# TK90X.net
KiCad netlist of a schematic drawn in EAGLE
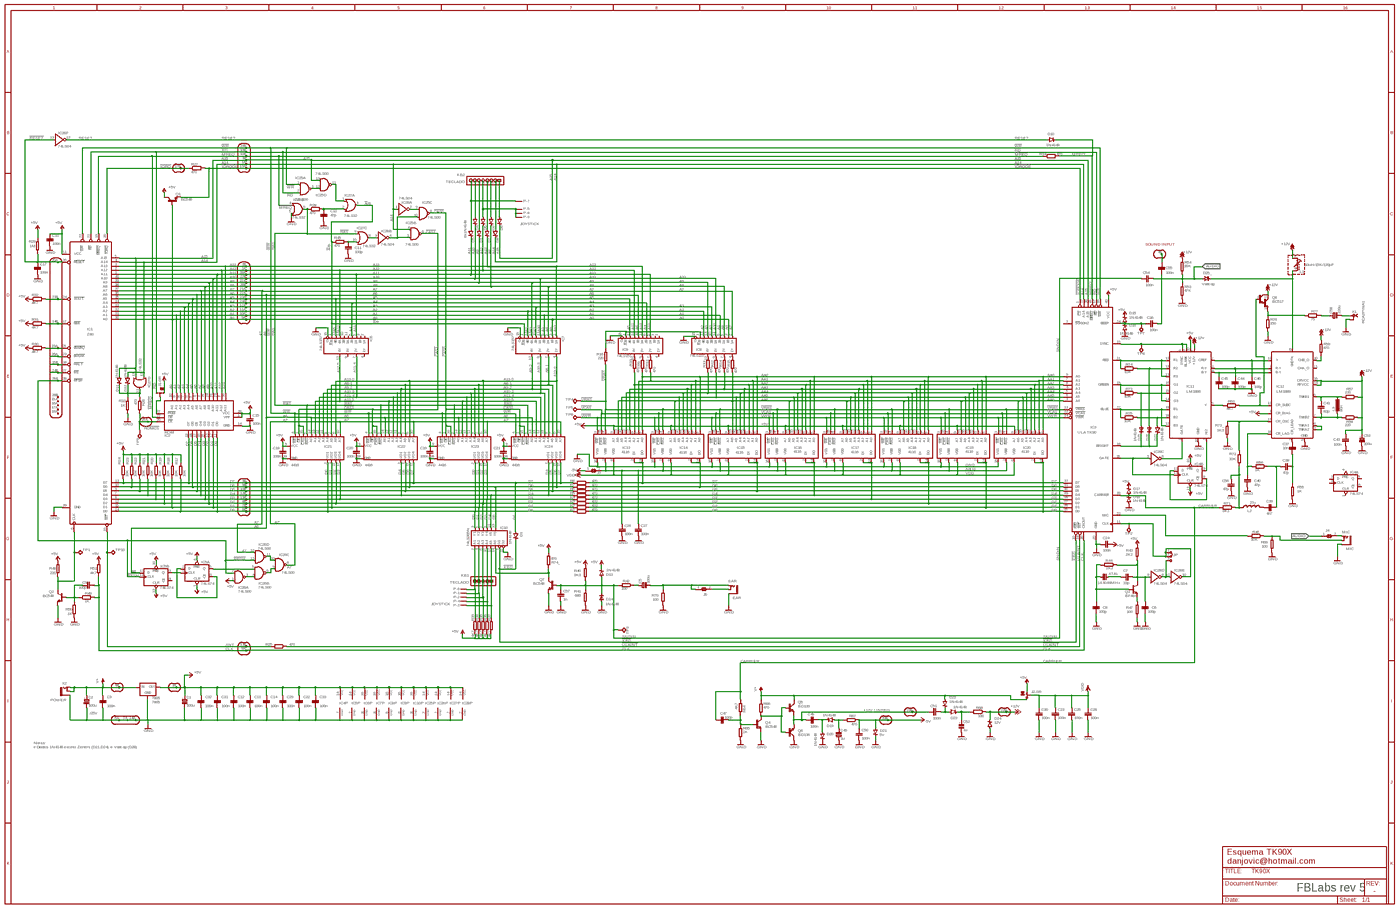
[diagram p0: schematic, sheet 1, overview]
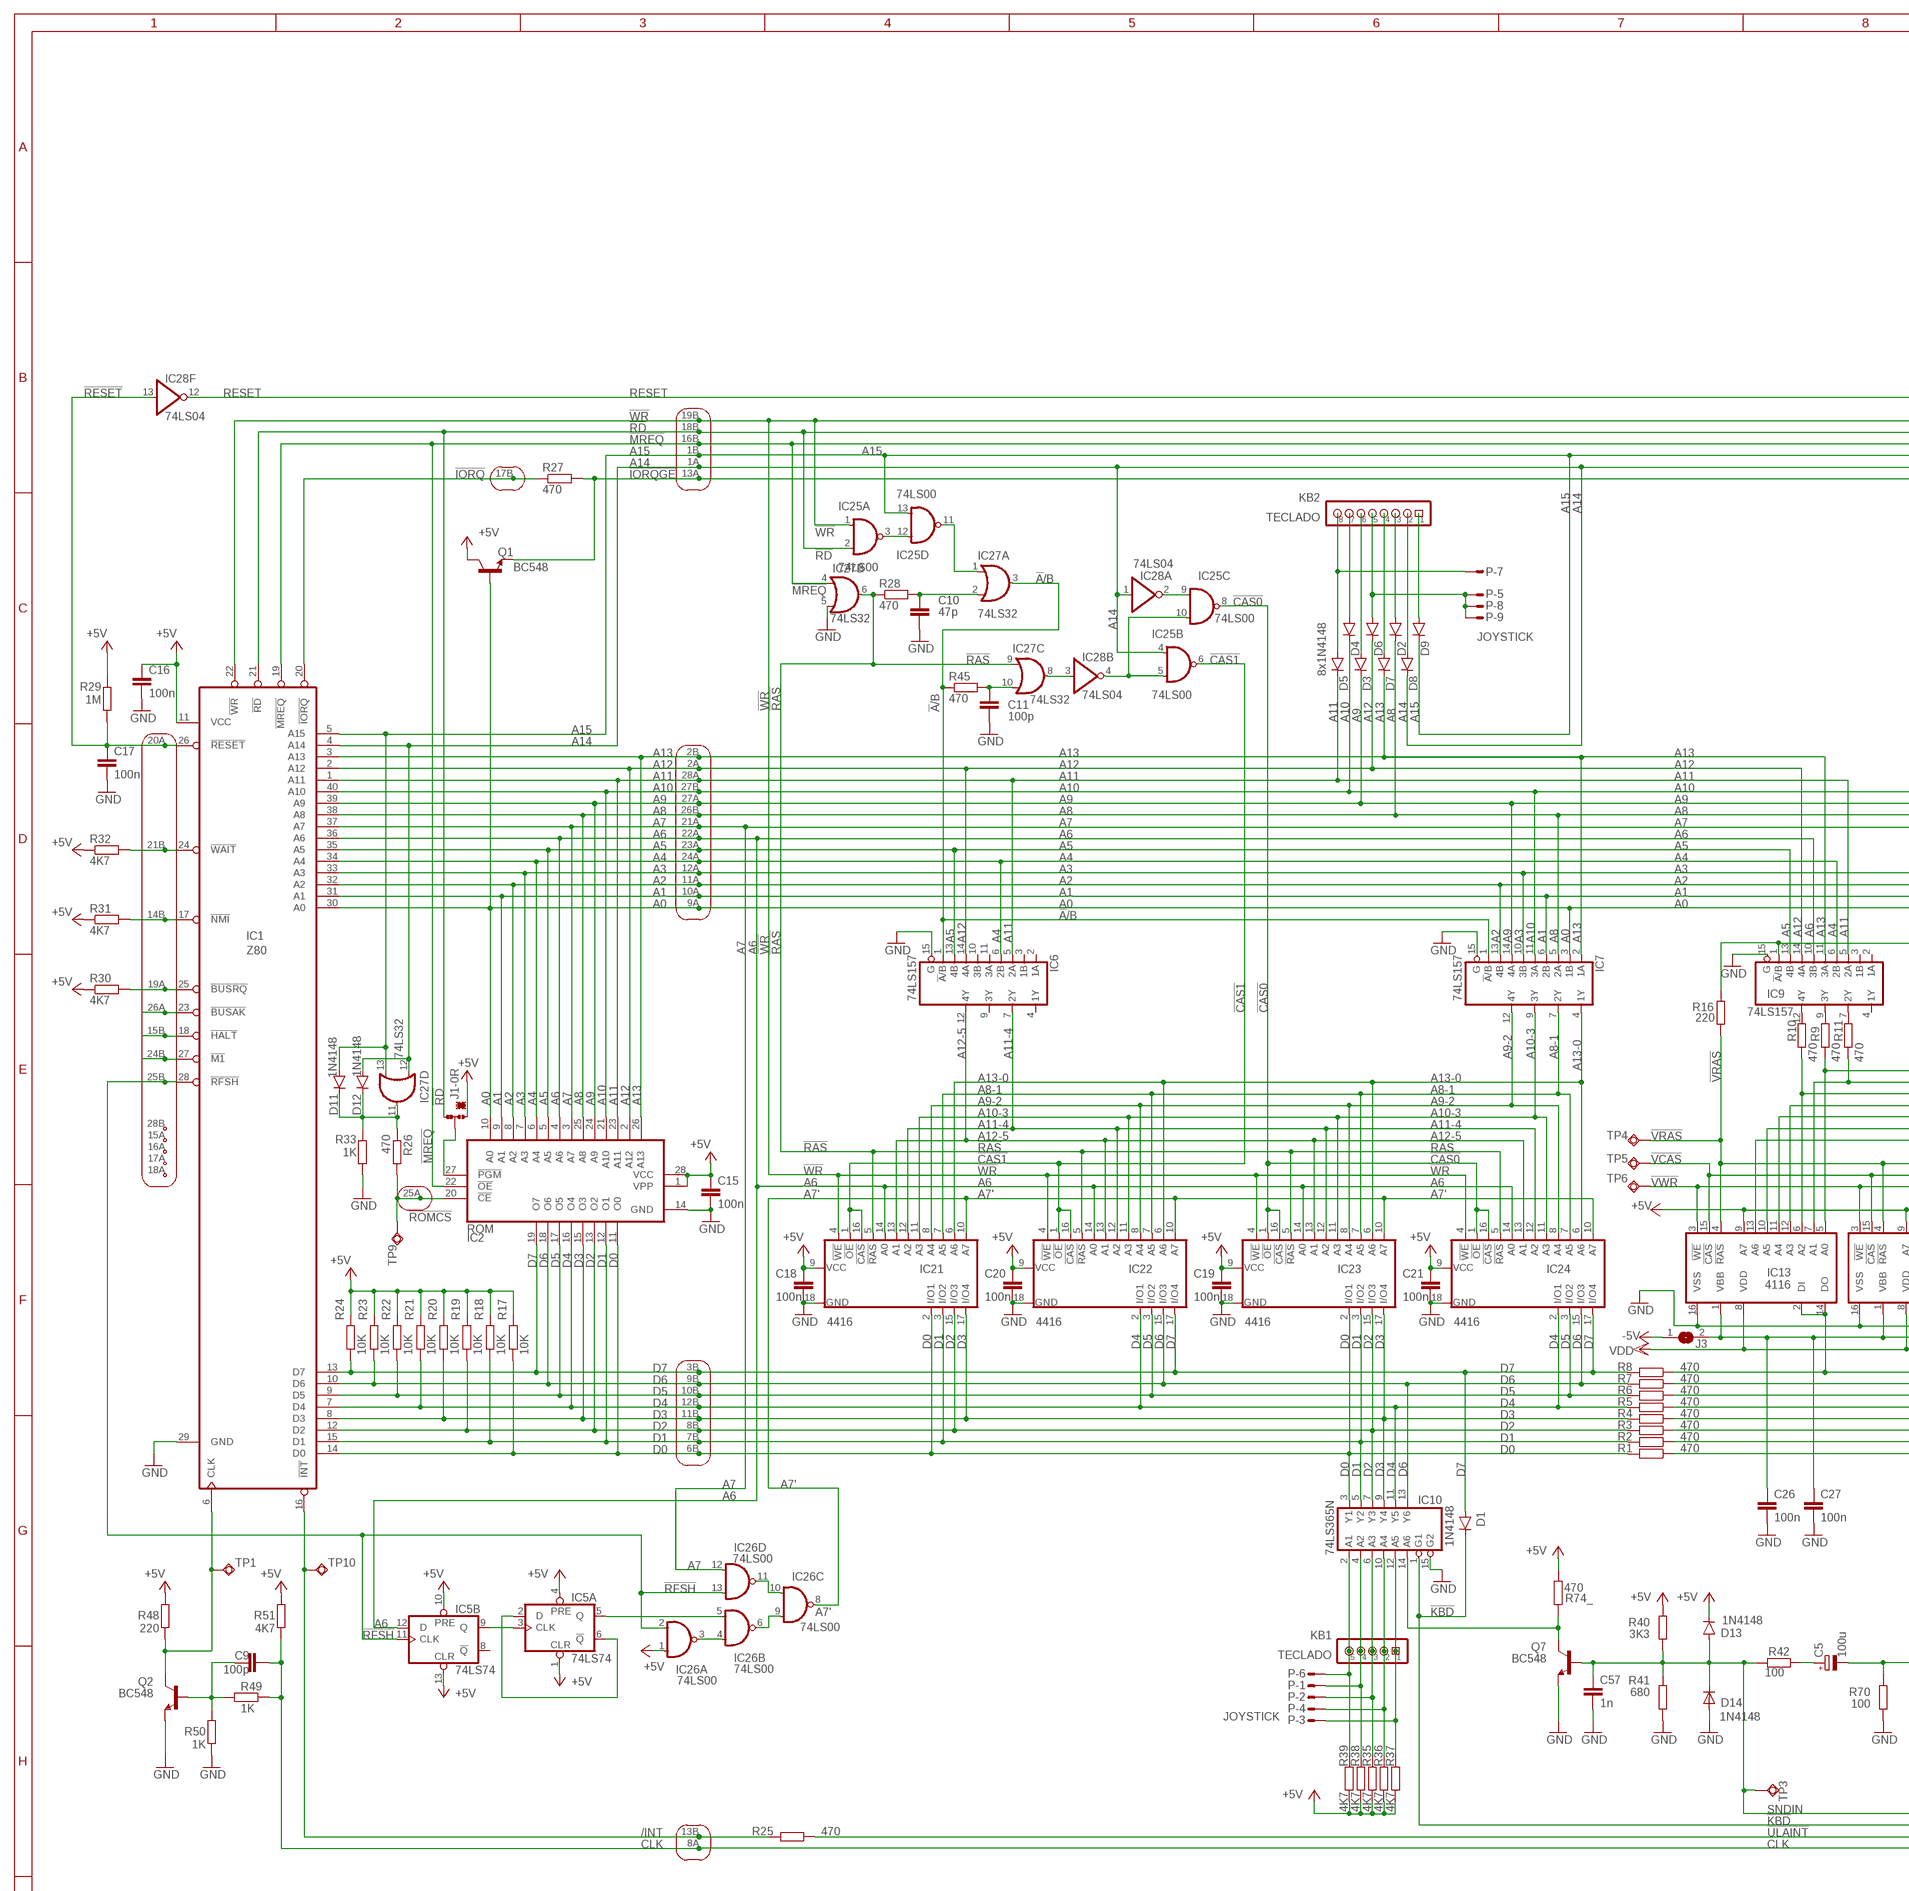
[diagram p1: schematic, sheet 1, part 1 of 4]
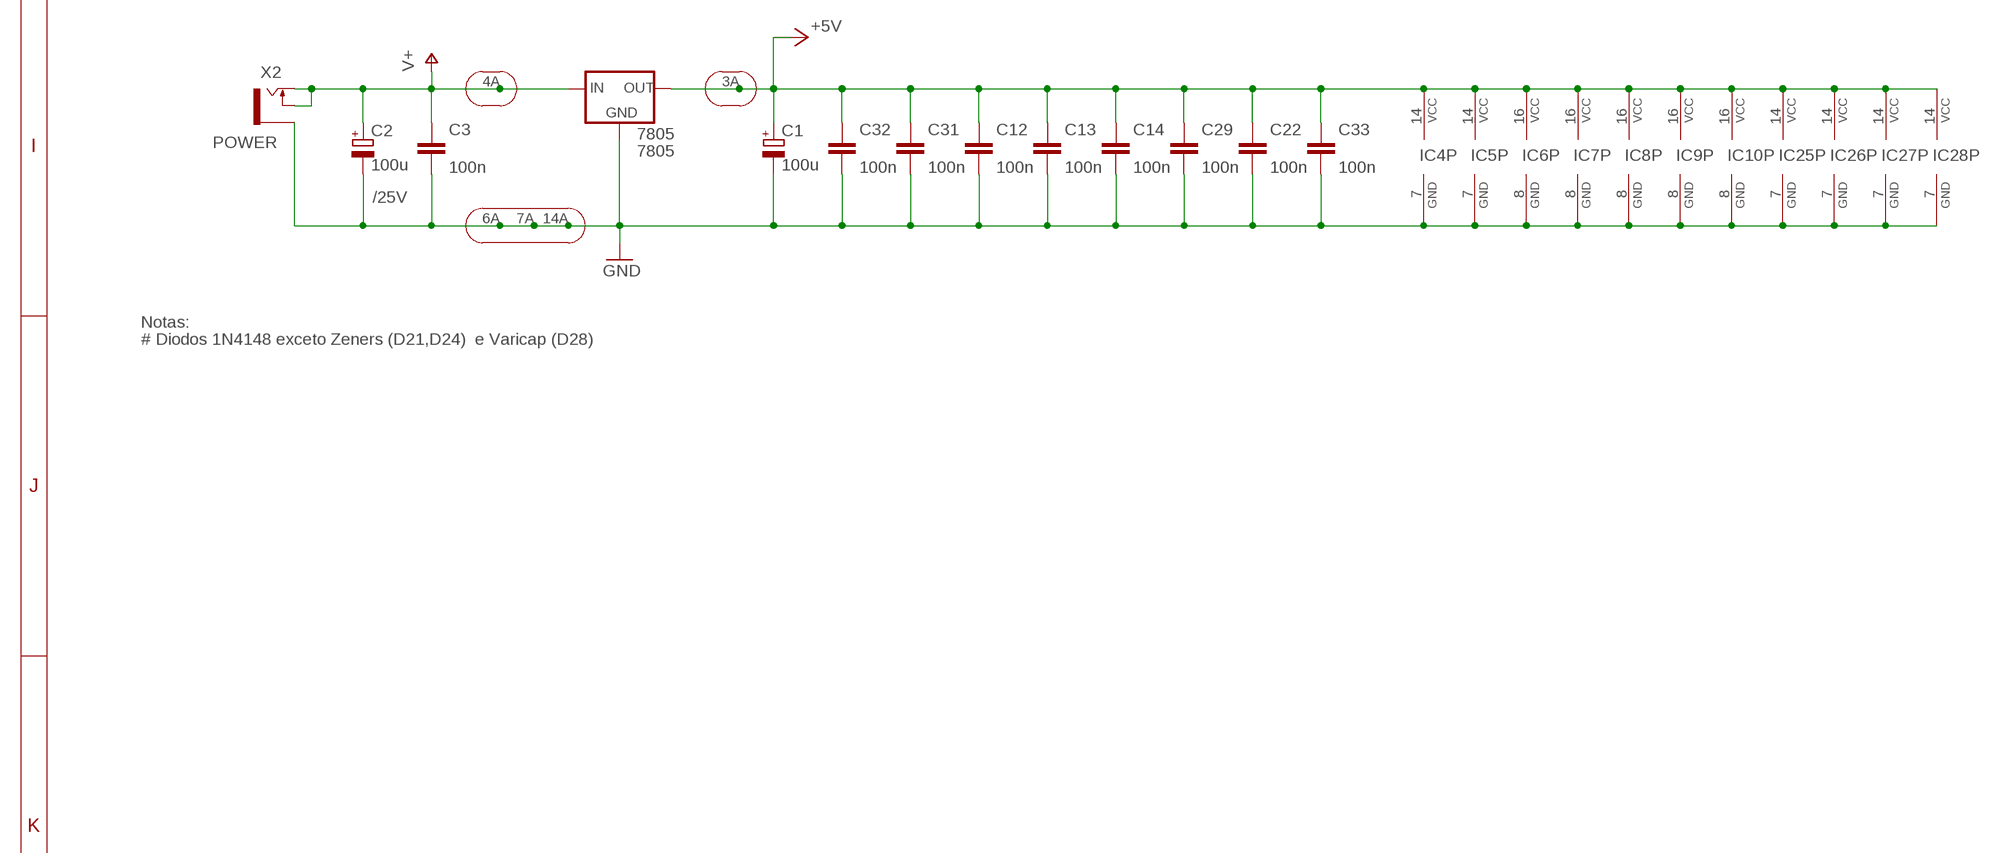
[diagram p2: schematic, sheet 1, part 2 of 4]
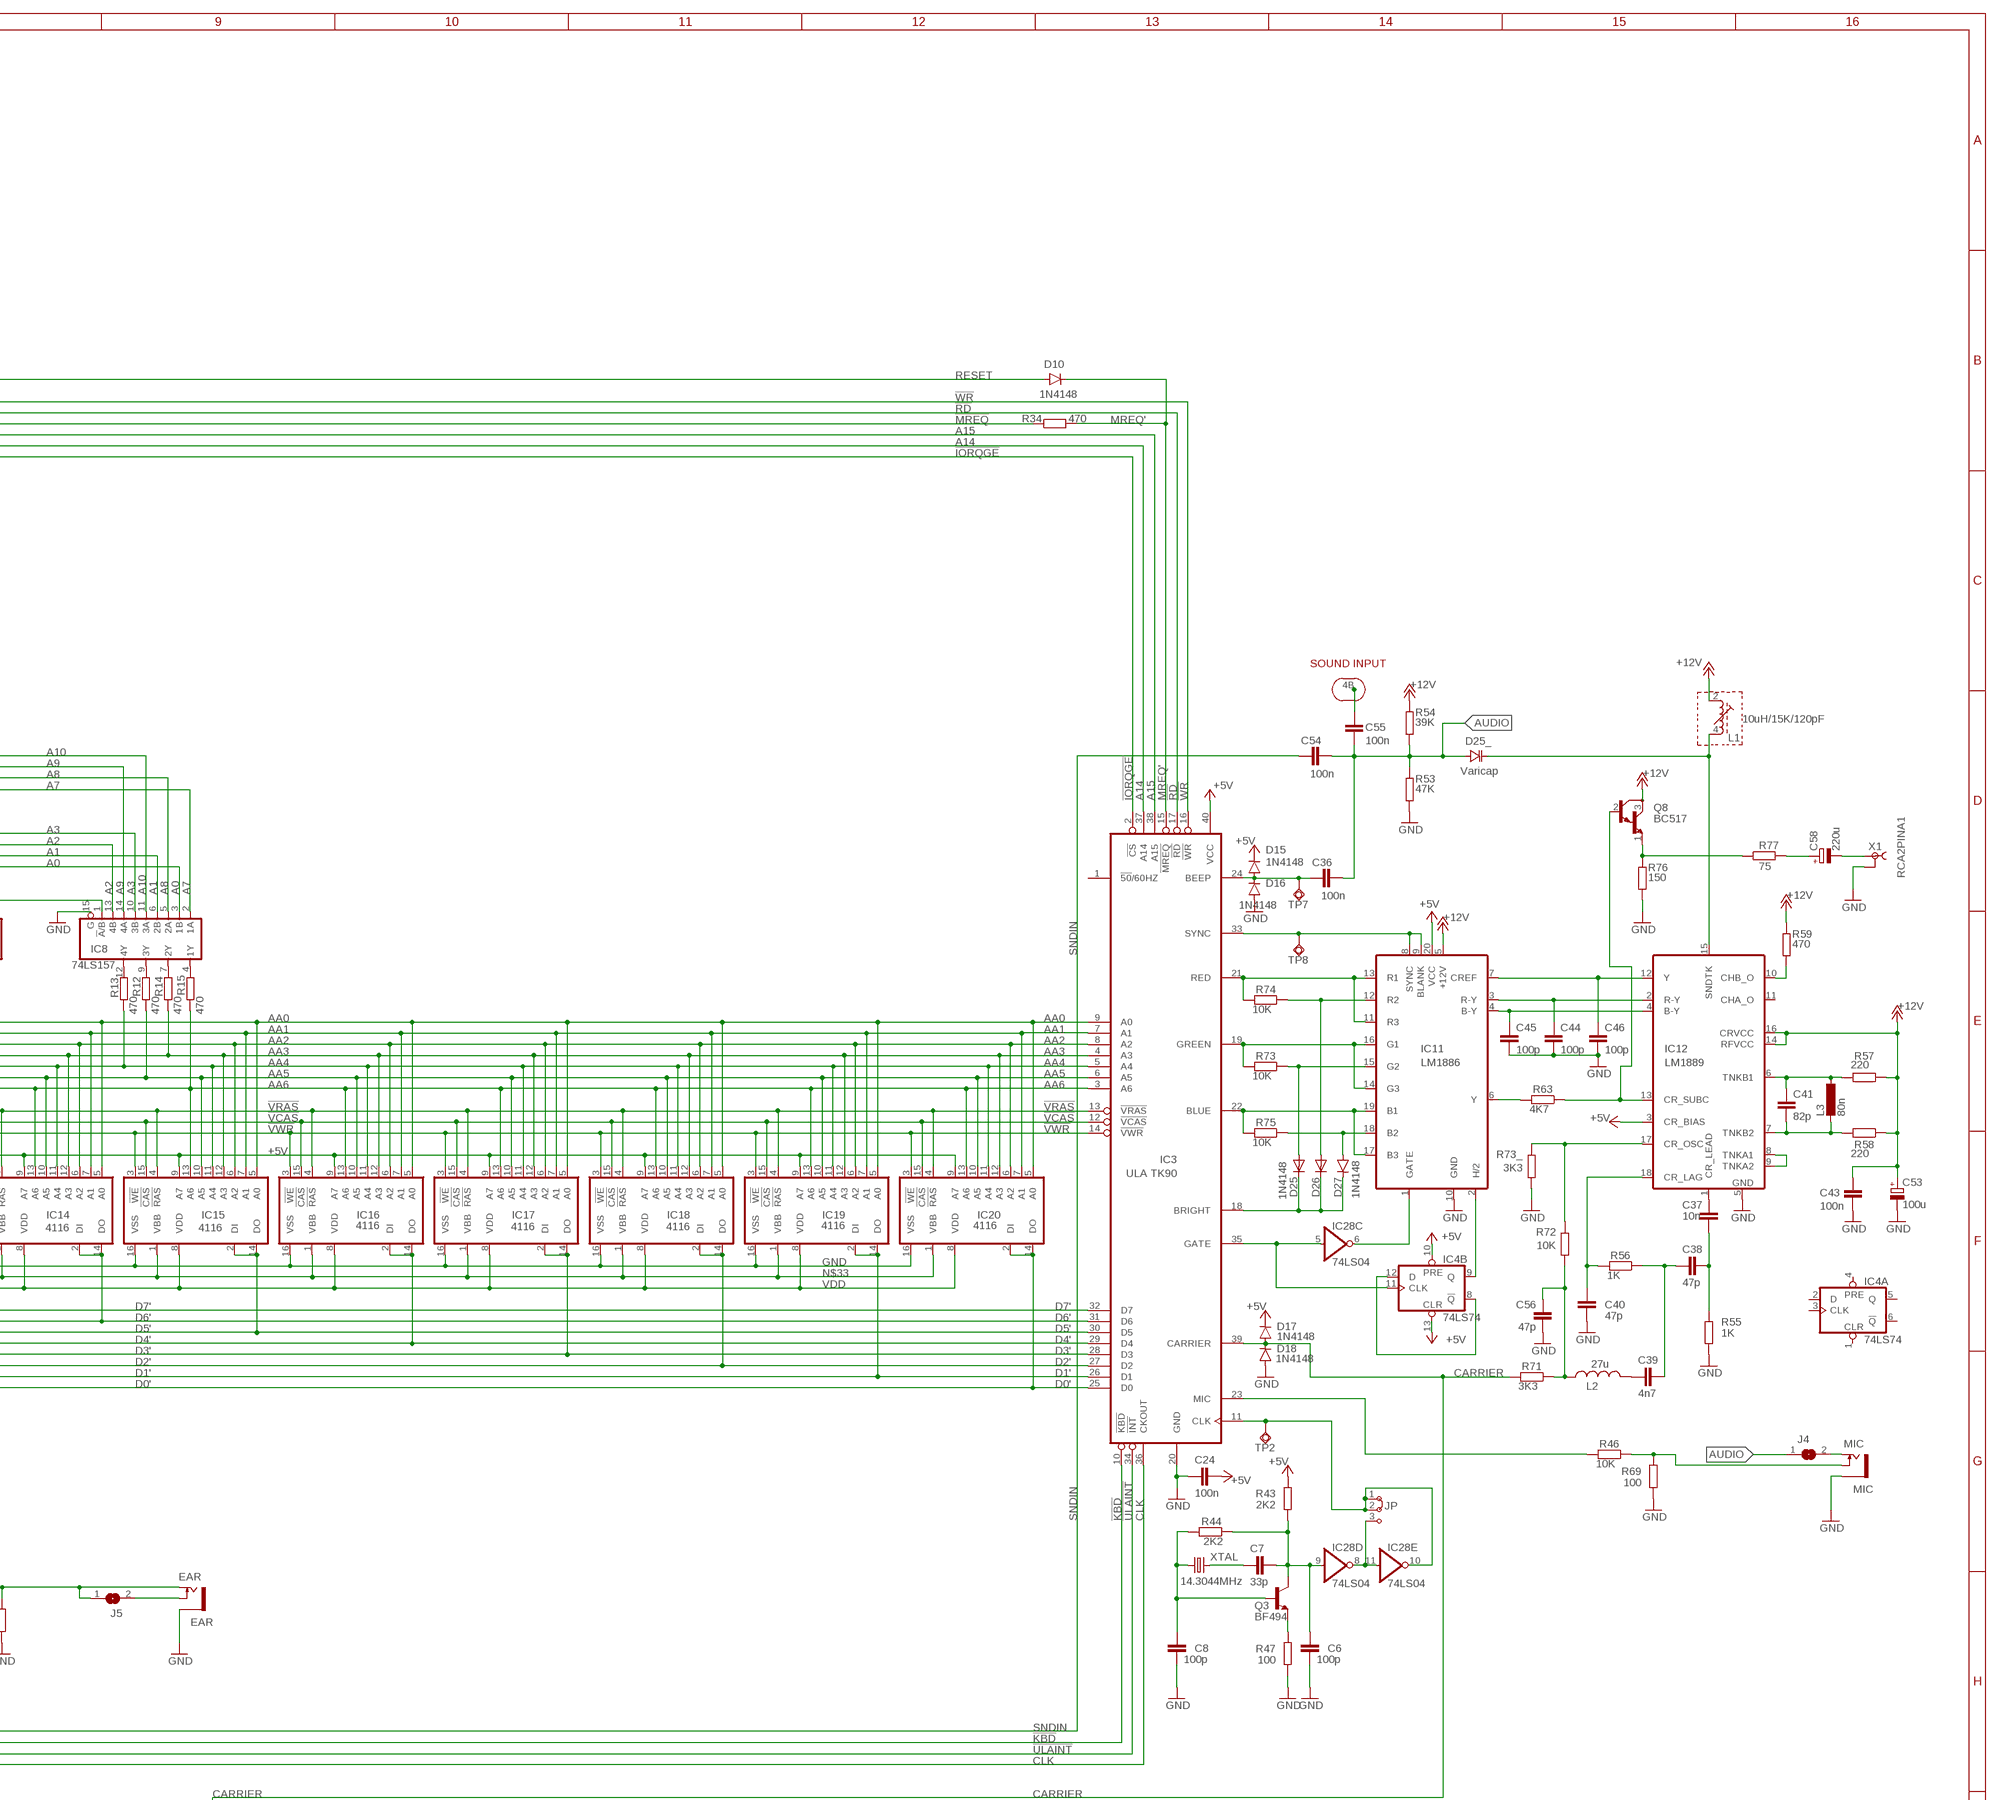
[diagram p3: schematic, sheet 1, part 3 of 4]
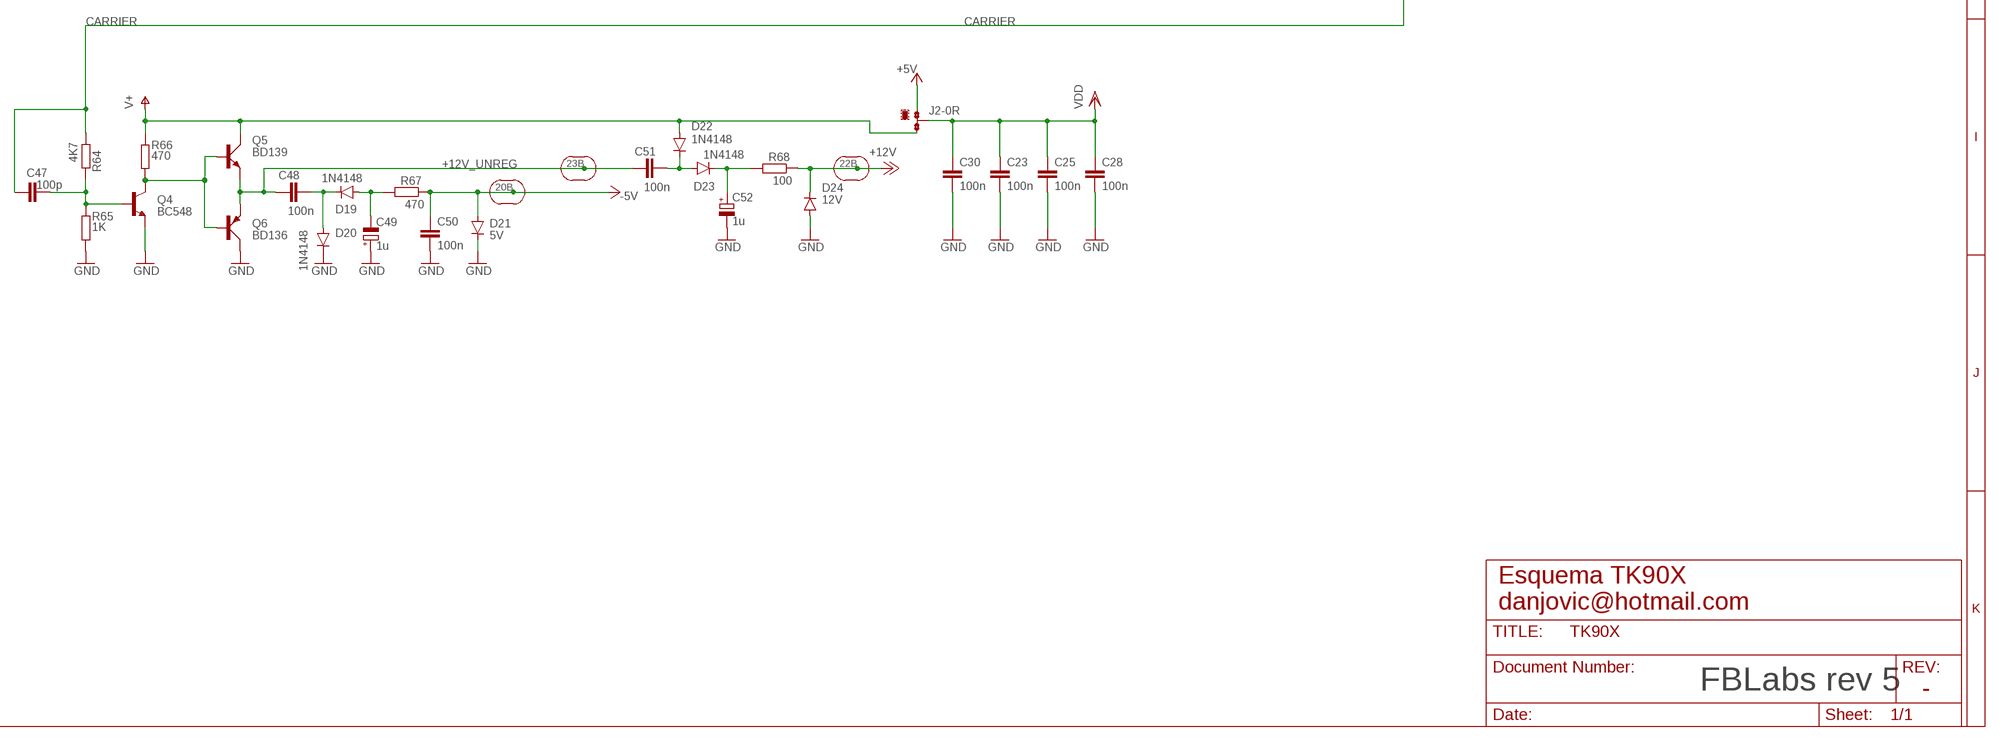
[diagram p4: schematic, sheet 1, part 4 of 4]

(export (version "E")
  (design (tool "Eeschema 10.0.6"))
  (components
    (comp (ref "7805")
      (value "7805")
      (footprint "eagle-import:78XXL")
      (libsource (lib "eagle-import") (part "78XXL"))
    )
    (comp (ref "C1")
      (value "100u")
      (footprint "eagle-import:E5-8,5")
      (libsource (lib "eagle-import") (part "CPOL-EUE5-8.5"))
    )
    (comp (ref "C2")
      (value "100u")
      (footprint "eagle-import:E5-8,5")
      (libsource (lib "eagle-import") (part "CPOL-EUE5-8.5"))
    )
    (comp (ref "C3")
      (value "100n")
      (footprint "eagle-import:C050-024X044")
      (libsource (lib "eagle-import") (part "C-EU050-024X044"))
    )
    (comp (ref "C5")
      (value "100u")
      (footprint "eagle-import:E5-4")
      (libsource (lib "eagle-import") (part "CPOL-EUE5-4"))
    )
    (comp (ref "C6")
      (value "100p")
      (footprint "eagle-import:C050-024X044")
      (libsource (lib "eagle-import") (part "C-EU050-024X044"))
    )
    (comp (ref "C7")
      (value "33p")
      (footprint "eagle-import:C050-024X044")
      (libsource (lib "eagle-import") (part "C-EU050-024X044"))
    )
    (comp (ref "C8")
      (value "100p")
      (footprint "eagle-import:C050-024X044")
      (libsource (lib "eagle-import") (part "C-EU050-024X044"))
    )
    (comp (ref "C9")
      (value "100p")
      (footprint "eagle-import:C050-024X044")
      (libsource (lib "eagle-import") (part "C-EU050-024X044"))
    )
    (comp (ref "C10")
      (value "47p")
      (footprint "eagle-import:C050-024X044")
      (libsource (lib "eagle-import") (part "C-EU050-024X044"))
    )
    (comp (ref "C11")
      (value "100p")
      (footprint "eagle-import:C050-024X044")
      (libsource (lib "eagle-import") (part "C-EU050-024X044"))
    )
    (comp (ref "C12")
      (value "100n")
      (footprint "eagle-import:C050-024X044")
      (libsource (lib "eagle-import") (part "C-EU050-024X044"))
    )
    (comp (ref "C13")
      (value "100n")
      (footprint "eagle-import:C050-024X044")
      (libsource (lib "eagle-import") (part "C-EU050-024X044"))
    )
    (comp (ref "C14")
      (value "100n")
      (footprint "eagle-import:C050-024X044")
      (libsource (lib "eagle-import") (part "C-EU050-024X044"))
    )
    (comp (ref "C15")
      (value "100n")
      (footprint "eagle-import:C050-024X044")
      (libsource (lib "eagle-import") (part "C-EU050-024X044"))
    )
    (comp (ref "C16")
      (value "100n")
      (footprint "eagle-import:C050-024X044")
      (libsource (lib "eagle-import") (part "C-EU050-024X044"))
    )
    (comp (ref "C17")
      (value "100n")
      (footprint "eagle-import:C050-024X044")
      (libsource (lib "eagle-import") (part "C-EU050-024X044"))
    )
    (comp (ref "C18")
      (value "100n")
      (footprint "eagle-import:C050-024X044")
      (libsource (lib "eagle-import") (part "C-EU050-024X044"))
    )
    (comp (ref "C19")
      (value "100n")
      (footprint "eagle-import:C050-024X044")
      (libsource (lib "eagle-import") (part "C-EU050-024X044"))
    )
    (comp (ref "C20")
      (value "100n")
      (footprint "eagle-import:C050-024X044")
      (libsource (lib "eagle-import") (part "C-EU050-024X044"))
    )
    (comp (ref "C21")
      (value "100n")
      (footprint "eagle-import:C050-024X044")
      (libsource (lib "eagle-import") (part "C-EU050-024X044"))
    )
    (comp (ref "C22")
      (value "100n")
      (footprint "eagle-import:C050-024X044")
      (libsource (lib "eagle-import") (part "C-EU050-024X044"))
    )
    (comp (ref "C23")
      (value "100n")
      (footprint "eagle-import:C050-024X044")
      (libsource (lib "eagle-import") (part "C-EU050-024X044"))
    )
    (comp (ref "C24")
      (value "100n")
      (footprint "eagle-import:C050-024X044")
      (libsource (lib "eagle-import") (part "C-EU050-024X044"))
    )
    (comp (ref "C25")
      (value "100n")
      (footprint "eagle-import:C050-024X044")
      (libsource (lib "eagle-import") (part "C-EU050-024X044"))
    )
    (comp (ref "C26")
      (value "100n")
      (footprint "eagle-import:C050-024X044")
      (libsource (lib "eagle-import") (part "C-EU050-024X044"))
    )
    (comp (ref "C27")
      (value "100n")
      (footprint "eagle-import:C050-024X044")
      (libsource (lib "eagle-import") (part "C-EU050-024X044"))
    )
    (comp (ref "C28")
      (value "100n")
      (footprint "eagle-import:C050-024X044")
      (libsource (lib "eagle-import") (part "C-EU050-024X044"))
    )
    (comp (ref "C29")
      (value "100n")
      (footprint "eagle-import:C050-024X044")
      (libsource (lib "eagle-import") (part "C-EU050-024X044"))
    )
    (comp (ref "C30")
      (value "100n")
      (footprint "eagle-import:C050-024X044")
      (libsource (lib "eagle-import") (part "C-EU050-024X044"))
    )
    (comp (ref "C31")
      (value "100n")
      (footprint "eagle-import:C050-024X044")
      (libsource (lib "eagle-import") (part "C-EU050-024X044"))
    )
    (comp (ref "C32")
      (value "100n")
      (footprint "eagle-import:C050-024X044")
      (libsource (lib "eagle-import") (part "C-EU050-024X044"))
    )
    (comp (ref "C33")
      (value "100n")
      (footprint "eagle-import:C050-024X044")
      (libsource (lib "eagle-import") (part "C-EU050-024X044"))
    )
    (comp (ref "C36")
      (value "100n")
      (footprint "eagle-import:C050-024X044")
      (libsource (lib "eagle-import") (part "C-EU050-024X044"))
    )
    (comp (ref "C37")
      (value "10n")
      (footprint "eagle-import:C050-024X044")
      (libsource (lib "eagle-import") (part "C-EU050-024X044"))
    )
    (comp (ref "C38")
      (value "47p")
      (footprint "eagle-import:C050-024X044")
      (libsource (lib "eagle-import") (part "C-EU050-024X044"))
    )
    (comp (ref "C39")
      (value "4n7")
      (footprint "eagle-import:C050-024X044")
      (libsource (lib "eagle-import") (part "C-EU050-024X044"))
    )
    (comp (ref "C40")
      (value "47p")
      (footprint "eagle-import:C050-024X044")
      (libsource (lib "eagle-import") (part "C-EU050-024X044"))
    )
    (comp (ref "C41")
      (value "82p")
      (footprint "eagle-import:C050-024X044")
      (libsource (lib "eagle-import") (part "C-EU050-024X044"))
    )
    (comp (ref "C43")
      (value "100n")
      (footprint "eagle-import:C050-024X044")
      (libsource (lib "eagle-import") (part "C-EU050-024X044"))
    )
    (comp (ref "C44")
      (value "100p")
      (footprint "eagle-import:C050-024X044")
      (libsource (lib "eagle-import") (part "C-EU050-024X044"))
    )
    (comp (ref "C45")
      (value "100p")
      (footprint "eagle-import:C050-024X044")
      (libsource (lib "eagle-import") (part "C-EU050-024X044"))
    )
    (comp (ref "C46")
      (value "100p")
      (footprint "eagle-import:C050-024X044")
      (libsource (lib "eagle-import") (part "C-EU050-024X044"))
    )
    (comp (ref "C47")
      (value "100p")
      (footprint "eagle-import:C050-024X044")
      (libsource (lib "eagle-import") (part "C-EU050-024X044"))
    )
    (comp (ref "C48")
      (value "100n")
      (footprint "eagle-import:C050-024X044")
      (libsource (lib "eagle-import") (part "C-EU050-024X044"))
    )
    (comp (ref "C49")
      (value "1u")
      (footprint "eagle-import:E2-4")
      (libsource (lib "eagle-import") (part "CPOL-EUE2-4"))
    )
    (comp (ref "C50")
      (value "100n")
      (footprint "eagle-import:C050-024X044")
      (libsource (lib "eagle-import") (part "C-EU050-024X044"))
    )
    (comp (ref "C51")
      (value "100n")
      (footprint "eagle-import:C050-024X044")
      (libsource (lib "eagle-import") (part "C-EU050-024X044"))
    )
    (comp (ref "C52")
      (value "1u")
      (footprint "eagle-import:E2-5")
      (libsource (lib "eagle-import") (part "CPOL-EUE2-5"))
    )
    (comp (ref "C53")
      (value "100u")
      (footprint "eagle-import:E5-4")
      (libsource (lib "eagle-import") (part "CPOL-EUE5-4"))
    )
    (comp (ref "C54")
      (value "100n")
      (footprint "eagle-import:C050-024X044")
      (libsource (lib "eagle-import") (part "C-EU050-024X044"))
    )
    (comp (ref "C55")
      (value "100n")
      (footprint "eagle-import:C050-024X044")
      (libsource (lib "eagle-import") (part "C-EU050-024X044"))
    )
    (comp (ref "C56")
      (value "47p")
      (footprint "eagle-import:C050-024X044")
      (libsource (lib "eagle-import") (part "C-EU050-024X044"))
    )
    (comp (ref "C57")
      (value "1n")
      (footprint "eagle-import:C050-024X044")
      (libsource (lib "eagle-import") (part "C-EU050-024X044"))
    )
    (comp (ref "C58")
      (value "220u")
      (footprint "eagle-import:E5-6")
      (libsource (lib "eagle-import") (part "CPOL-EUE5-6"))
    )
    (comp (ref "D1")
      (value "1N4148")
      (footprint "eagle-import:DO35-12")
      (libsource (lib "eagle-import") (part "DDO35-12"))
    )
    (comp (ref "D2")
      (value "1N4148")
      (footprint "eagle-import:DO35-12")
      (libsource (lib "eagle-import") (part "DDO35-12"))
    )
    (comp (ref "D3")
      (value "1N4148")
      (footprint "eagle-import:DO35-12")
      (libsource (lib "eagle-import") (part "DDO35-12"))
    )
    (comp (ref "D4")
      (value "1N4148")
      (footprint "eagle-import:DO35-12")
      (libsource (lib "eagle-import") (part "DDO35-12"))
    )
    (comp (ref "D5")
      (value "1N4148")
      (footprint "eagle-import:DO35-12")
      (libsource (lib "eagle-import") (part "DDO35-12"))
    )
    (comp (ref "D6")
      (value "1N4148")
      (footprint "eagle-import:DO35-12")
      (libsource (lib "eagle-import") (part "DDO35-12"))
    )
    (comp (ref "D7")
      (value "1N4148")
      (footprint "eagle-import:DO35-12")
      (libsource (lib "eagle-import") (part "DDO35-12"))
    )
    (comp (ref "D8")
      (value "1N4148")
      (footprint "eagle-import:DO35-12")
      (libsource (lib "eagle-import") (part "DDO35-12"))
    )
    (comp (ref "D9")
      (value "1N4148")
      (footprint "eagle-import:DO35-12")
      (libsource (lib "eagle-import") (part "DDO35-12"))
    )
    (comp (ref "D10")
      (value "1N4148")
      (footprint "eagle-import:DO35-12")
      (libsource (lib "eagle-import") (part "DDO35-12"))
    )
    (comp (ref "D11")
      (value "1N4148")
      (footprint "eagle-import:DO35-12")
      (libsource (lib "eagle-import") (part "DDO35-12"))
    )
    (comp (ref "D12")
      (value "1N4148")
      (footprint "eagle-import:DO35-12")
      (libsource (lib "eagle-import") (part "DDO35-12"))
    )
    (comp (ref "D13")
      (value "1N4148")
      (footprint "eagle-import:DO35-12")
      (libsource (lib "eagle-import") (part "DDO35-12"))
    )
    (comp (ref "D14")
      (value "1N4148")
      (footprint "eagle-import:D-5")
      (libsource (lib "eagle-import") (part "DIODE-D-5"))
    )
    (comp (ref "D15")
      (value "1N4148")
      (footprint "eagle-import:DO35-12")
      (libsource (lib "eagle-import") (part "DDO35-12"))
    )
    (comp (ref "D16")
      (value "1N4148")
      (footprint "eagle-import:DO35-12")
      (libsource (lib "eagle-import") (part "DDO35-12"))
    )
    (comp (ref "D17")
      (value "1N4148")
      (footprint "eagle-import:DO35-12")
      (libsource (lib "eagle-import") (part "DDO35-12"))
    )
    (comp (ref "D18")
      (value "1N4148")
      (footprint "eagle-import:DO35-12")
      (libsource (lib "eagle-import") (part "DDO35-12"))
    )
    (comp (ref "D19")
      (value "1N4148")
      (footprint "eagle-import:DO35-12")
      (libsource (lib "eagle-import") (part "DDO35-12"))
    )
    (comp (ref "D20")
      (value "1N4148")
      (footprint "eagle-import:DO35-12")
      (libsource (lib "eagle-import") (part "DDO35-12"))
    )
    (comp (ref "D21")
      (value "5V")
      (footprint "eagle-import:DO35-12")
      (libsource (lib "eagle-import") (part "DDO35-12"))
    )
    (comp (ref "D22")
      (value "1N4148")
      (footprint "eagle-import:DO35-12")
      (libsource (lib "eagle-import") (part "DDO35-12"))
    )
    (comp (ref "D23")
      (value "1N4148")
      (footprint "eagle-import:DO35-12")
      (libsource (lib "eagle-import") (part "DDO35-12"))
    )
    (comp (ref "D24")
      (value "12V")
      (footprint "eagle-import:DO35-12")
      (libsource (lib "eagle-import") (part "DDO35-12"))
    )
    (comp (ref "D25")
      (value "1N4148")
      (footprint "eagle-import:D-5")
      (libsource (lib "eagle-import") (part "DIODE-D-5"))
    )
    (comp (ref "D25_")
      (value "Varicap")
      (footprint "eagle-import:D200")
      (libsource (lib "eagle-import") (part "VARICAP-200"))
    )
    (comp (ref "D26")
      (value "1N4148")
      (footprint "eagle-import:D-5")
      (libsource (lib "eagle-import") (part "DIODE-D-5"))
    )
    (comp (ref "D27")
      (value "1N4148")
      (footprint "eagle-import:DO35-12")
      (libsource (lib "eagle-import") (part "DDO35-12"))
    )
    (comp (ref "EAR")
      (value "EAR")
      (footprint "eagle-import:MONO")
      (libsource (lib "eagle-import") (part "JACK?-MONO"))
    )
    (comp (ref "IC1")
      (value "Z80")
      (footprint "eagle-import:DIL40")
      (libsource (lib "eagle-import") (part "Z80CPU"))
    )
    (comp (ref "IC2")
      (value "ROM")
      (footprint "eagle-import:DIL28")
      (libsource (lib "eagle-import") (part "25128"))
    )
    (comp (ref "IC3")
      (value "ULA TK90")
      (footprint "eagle-import:DIL40")
      (libsource (lib "eagle-import") (part "ULA-TK90"))
    )
    (comp (ref "IC4")
      (value "74LS74")
      (footprint "eagle-import:DIL14")
      (libsource (lib "eagle-import") (part "7474NLS"))
    )
    (comp (ref "IC5")
      (value "74LS74")
      (footprint "eagle-import:DIL14")
      (libsource (lib "eagle-import") (part "7474NLS"))
    )
    (comp (ref "IC6")
      (value "74LS157")
      (footprint "eagle-import:DIL16")
      (libsource (lib "eagle-import") (part "74157NS"))
    )
    (comp (ref "IC7")
      (value "74LS157")
      (footprint "eagle-import:DIL16")
      (libsource (lib "eagle-import") (part "74157NS"))
    )
    (comp (ref "IC8")
      (value "74LS157")
      (footprint "eagle-import:DIL16")
      (libsource (lib "eagle-import") (part "74157NS"))
    )
    (comp (ref "IC9")
      (value "74LS157")
      (footprint "eagle-import:DIL16")
      (libsource (lib "eagle-import") (part "74157NS"))
    )
    (comp (ref "IC10")
      (value "74LS365N")
      (footprint "eagle-import:DIL16")
      (libsource (lib "eagle-import") (part "74365NLS"))
    )
    (comp (ref "IC11")
      (value "LM1886")
      (footprint "eagle-import:DIL20")
      (libsource (lib "eagle-import") (part "LM1886N"))
    )
    (comp (ref "IC12")
      (value "LM1889")
      (footprint "eagle-import:DIL18")
      (libsource (lib "eagle-import") (part "LM1889"))
    )
    (comp (ref "IC13")
      (value "4116")
      (footprint "eagle-import:DIL16")
      (libsource (lib "eagle-import") (part "MK4516"))
    )
    (comp (ref "IC14")
      (value "4116")
      (footprint "eagle-import:DIL16")
      (libsource (lib "eagle-import") (part "MK4516"))
    )
    (comp (ref "IC15")
      (value "4116")
      (footprint "eagle-import:DIL16")
      (libsource (lib "eagle-import") (part "MK4516"))
    )
    (comp (ref "IC16")
      (value "4116")
      (footprint "eagle-import:DIL16")
      (libsource (lib "eagle-import") (part "MK4516"))
    )
    (comp (ref "IC17")
      (value "4116")
      (footprint "eagle-import:DIL16")
      (libsource (lib "eagle-import") (part "MK4516"))
    )
    (comp (ref "IC18")
      (value "4116")
      (footprint "eagle-import:DIL16")
      (libsource (lib "eagle-import") (part "MK4516"))
    )
    (comp (ref "IC19")
      (value "4116")
      (footprint "eagle-import:DIL16")
      (libsource (lib "eagle-import") (part "MK4516"))
    )
    (comp (ref "IC20")
      (value "4116")
      (footprint "eagle-import:DIL16")
      (libsource (lib "eagle-import") (part "MK4516"))
    )
    (comp (ref "IC21")
      (value "4416")
      (footprint "eagle-import:DIL18")
      (libsource (lib "eagle-import") (part "4416"))
    )
    (comp (ref "IC22")
      (value "4416")
      (footprint "eagle-import:DIL18")
      (libsource (lib "eagle-import") (part "4416"))
    )
    (comp (ref "IC23")
      (value "4416")
      (footprint "eagle-import:DIL18")
      (libsource (lib "eagle-import") (part "4416"))
    )
    (comp (ref "IC24")
      (value "4416")
      (footprint "eagle-import:DIL18")
      (libsource (lib "eagle-import") (part "4416"))
    )
    (comp (ref "IC25")
      (value "74LS00")
      (footprint "eagle-import:DIL14")
      (libsource (lib "eagle-import") (part "7400NLS"))
    )
    (comp (ref "IC26")
      (value "74LS00")
      (footprint "eagle-import:DIL14")
      (libsource (lib "eagle-import") (part "7400NLS"))
    )
    (comp (ref "IC27")
      (value "74LS32")
      (footprint "eagle-import:DIL14")
      (libsource (lib "eagle-import") (part "7432NLS"))
    )
    (comp (ref "IC28")
      (value "74LS04")
      (footprint "eagle-import:DIL14")
      (libsource (lib "eagle-import") (part "7404NLS"))
    )
    (comp (ref "J1")
      (value "0R-JUMPB")
      (footprint "eagle-import:B0R-JMP")
      (libsource (lib "eagle-import") (part "0R-JUMPB"))
    )
    (comp (ref "J2")
      (value "0R-JUMPB")
      (footprint "eagle-import:B0R-JMP")
      (libsource (lib "eagle-import") (part "0R-JUMPB"))
    )
    (comp (ref "J3") (value "SJ") (footprint "eagle-import:SJ") (libsource (lib "eagle-import") (part "SJ")))
    (comp (ref "J4") (value "SJ") (footprint "eagle-import:SJ") (libsource (lib "eagle-import") (part "SJ")))
    (comp (ref "J5") (value "SJ") (footprint "eagle-import:SJ") (libsource (lib "eagle-import") (part "SJ")))
    (comp (ref "JP")
      (value "J2X1MM")
      (footprint "eagle-import:03C")
      (libsource (lib "eagle-import") (part "J2X1MM"))
    )
    (comp (ref "KB1")
      (value "TECLADO")
      (footprint "eagle-import:FE05-1")
      (libsource (lib "eagle-import") (part "CON-TECL-5"))
    )
    (comp (ref "KB2")
      (value "TECLADO")
      (footprint "eagle-import:FE08")
      (libsource (lib "eagle-import") (part "CON-TECL-8"))
    )
    (comp (ref "L1")
      (value "10uH/15K/120pF")
      (footprint "eagle-import:COIL")
      (libsource (lib "eagle-import") (part "COIL"))
    )
    (comp (ref "L2")
      (value "27u")
      (footprint "eagle-import:0207_7")
      (libsource (lib "eagle-import") (part "L-US0207/7"))
    )
    (comp (ref "L3")
      (value "80n")
      (footprint "eagle-import:0204_5")
      (libsource (lib "eagle-import") (part "L-EU0204/5"))
    )
    (comp (ref "MIC")
      (value "MIC")
      (footprint "eagle-import:MONO")
      (libsource (lib "eagle-import") (part "JACK?-MONO"))
    )
    (comp (ref "P")
      (value "JOYSTICK")
      (footprint "eagle-import:177-009-MALE")
      (libsource (lib "eagle-import") (part "M09?S.590"))
    )
    (comp (ref "Q1")
      (value "BC548")
      (footprint "eagle-import:TO92L")
      (libsource (lib "eagle-import") (part "-NPN-TO92L"))
    )
    (comp (ref "Q2")
      (value "BC548")
      (footprint "eagle-import:TO92L")
      (libsource (lib "eagle-import") (part "-NPN-TO92L"))
    )
    (comp (ref "Q3")
      (value "BF494")
      (footprint "eagle-import:TO92-CEB")
      (libsource (lib "eagle-import") (part "BF494"))
    )
    (comp (ref "Q4")
      (value "BC548")
      (footprint "eagle-import:TO92L")
      (libsource (lib "eagle-import") (part "-NPN-TO92L"))
    )
    (comp (ref "Q5")
      (value "BD139")
      (footprint "eagle-import:TO126AV")
      (libsource (lib "eagle-import") (part "BD139"))
    )
    (comp (ref "Q6")
      (value "BD136")
      (footprint "eagle-import:TO126AV")
      (libsource (lib "eagle-import") (part "BD140"))
    )
    (comp (ref "Q7")
      (value "BC548")
      (footprint "eagle-import:TO92L")
      (libsource (lib "eagle-import") (part "-NPN-TO92L"))
    )
    (comp (ref "Q8")
      (value "BC517")
      (footprint "eagle-import:TO92")
      (libsource (lib "eagle-import") (part "BC517"))
    )
    (comp (ref "R1")
      (value "470")
      (footprint "eagle-import:0207_12")
      (libsource (lib "eagle-import") (part "R-EU_0207/12"))
    )
    (comp (ref "R2")
      (value "470")
      (footprint "eagle-import:0207_12")
      (libsource (lib "eagle-import") (part "R-EU_0207/12"))
    )
    (comp (ref "R3")
      (value "470")
      (footprint "eagle-import:0207_12")
      (libsource (lib "eagle-import") (part "R-EU_0207/12"))
    )
    (comp (ref "R4")
      (value "470")
      (footprint "eagle-import:0207_12")
      (libsource (lib "eagle-import") (part "R-EU_0207/12"))
    )
    (comp (ref "R5")
      (value "470")
      (footprint "eagle-import:0207_12")
      (libsource (lib "eagle-import") (part "R-EU_0207/12"))
    )
    (comp (ref "R6")
      (value "470")
      (footprint "eagle-import:0207_12")
      (libsource (lib "eagle-import") (part "R-EU_0207/12"))
    )
    (comp (ref "R7")
      (value "470")
      (footprint "eagle-import:0207_12")
      (libsource (lib "eagle-import") (part "R-EU_0207/12"))
    )
    (comp (ref "R8")
      (value "470")
      (footprint "eagle-import:0207_12")
      (libsource (lib "eagle-import") (part "R-EU_0207/12"))
    )
    (comp (ref "R9")
      (value "470")
      (footprint "eagle-import:0207_12")
      (libsource (lib "eagle-import") (part "R-EU_0207/12"))
    )
    (comp (ref "R10")
      (value "470")
      (footprint "eagle-import:0207_12")
      (libsource (lib "eagle-import") (part "R-EU_0207/12"))
    )
    (comp (ref "R11")
      (value "470")
      (footprint "eagle-import:0207_12")
      (libsource (lib "eagle-import") (part "R-EU_0207/12"))
    )
    (comp (ref "R12")
      (value "470")
      (footprint "eagle-import:0207_12")
      (libsource (lib "eagle-import") (part "R-EU_0207/12"))
    )
    (comp (ref "R13")
      (value "470")
      (footprint "eagle-import:0207_12")
      (libsource (lib "eagle-import") (part "R-EU_0207/12"))
    )
    (comp (ref "R14")
      (value "470")
      (footprint "eagle-import:0207_12")
      (libsource (lib "eagle-import") (part "R-EU_0207/12"))
    )
    (comp (ref "R15")
      (value "470")
      (footprint "eagle-import:0207_12")
      (libsource (lib "eagle-import") (part "R-EU_0207/12"))
    )
    (comp (ref "R16")
      (value "220")
      (footprint "eagle-import:0207_12")
      (libsource (lib "eagle-import") (part "R-EU_0207/12"))
    )
    (comp (ref "R17")
      (value "10K")
      (footprint "eagle-import:0207_12")
      (libsource (lib "eagle-import") (part "R-EU_0207/12"))
    )
    (comp (ref "R18")
      (value "10K")
      (footprint "eagle-import:0207_12")
      (libsource (lib "eagle-import") (part "R-EU_0207/12"))
    )
    (comp (ref "R19")
      (value "10K")
      (footprint "eagle-import:0207_12")
      (libsource (lib "eagle-import") (part "R-EU_0207/12"))
    )
    (comp (ref "R20")
      (value "10K")
      (footprint "eagle-import:0207_12")
      (libsource (lib "eagle-import") (part "R-EU_0207/12"))
    )
    (comp (ref "R21")
      (value "10K")
      (footprint "eagle-import:0207_12")
      (libsource (lib "eagle-import") (part "R-EU_0207/12"))
    )
    (comp (ref "R22")
      (value "10K")
      (footprint "eagle-import:0207_12")
      (libsource (lib "eagle-import") (part "R-EU_0207/12"))
    )
    (comp (ref "R23")
      (value "10K")
      (footprint "eagle-import:0207_12")
      (libsource (lib "eagle-import") (part "R-EU_0207/12"))
    )
    (comp (ref "R24")
      (value "10K")
      (footprint "eagle-import:0207_12")
      (libsource (lib "eagle-import") (part "R-EU_0207/12"))
    )
    (comp (ref "R25")
      (value "470")
      (footprint "eagle-import:0207_12")
      (libsource (lib "eagle-import") (part "R-EU_0207/12"))
    )
    (comp (ref "R26")
      (value "470")
      (footprint "eagle-import:0207_12")
      (libsource (lib "eagle-import") (part "R-EU_0207/12"))
    )
    (comp (ref "R27")
      (value "470")
      (footprint "eagle-import:0207_12")
      (libsource (lib "eagle-import") (part "R-EU_0207/12"))
    )
    (comp (ref "R28")
      (value "470")
      (footprint "eagle-import:0207_12")
      (libsource (lib "eagle-import") (part "R-EU_0207/12"))
    )
    (comp (ref "R29")
      (value "1M")
      (footprint "eagle-import:0207_12")
      (libsource (lib "eagle-import") (part "R-EU_0207/12"))
    )
    (comp (ref "R30")
      (value "4K7")
      (footprint "eagle-import:0207_12")
      (libsource (lib "eagle-import") (part "R-EU_0207/12"))
    )
    (comp (ref "R31")
      (value "4K7")
      (footprint "eagle-import:0207_12")
      (libsource (lib "eagle-import") (part "R-EU_0207/12"))
    )
    (comp (ref "R32")
      (value "4K7")
      (footprint "eagle-import:0207_12")
      (libsource (lib "eagle-import") (part "R-EU_0207/12"))
    )
    (comp (ref "R33")
      (value "1K")
      (footprint "eagle-import:0207_12")
      (libsource (lib "eagle-import") (part "R-EU_0207/12"))
    )
    (comp (ref "R34")
      (value "470")
      (footprint "eagle-import:0207_12")
      (libsource (lib "eagle-import") (part "R-EU_0207/12"))
    )
    (comp (ref "R35")
      (value "4K7")
      (footprint "eagle-import:0207_12")
      (libsource (lib "eagle-import") (part "R-EU_0207/12"))
    )
    (comp (ref "R36")
      (value "4K7")
      (footprint "eagle-import:0207_12")
      (libsource (lib "eagle-import") (part "R-EU_0207/12"))
    )
    (comp (ref "R37")
      (value "4K7")
      (footprint "eagle-import:0207_12")
      (libsource (lib "eagle-import") (part "R-EU_0207/12"))
    )
    (comp (ref "R38")
      (value "4K7")
      (footprint "eagle-import:0207_12")
      (libsource (lib "eagle-import") (part "R-EU_0207/12"))
    )
    (comp (ref "R39")
      (value "4K7")
      (footprint "eagle-import:0207_12")
      (libsource (lib "eagle-import") (part "R-EU_0207/12"))
    )
    (comp (ref "R40")
      (value "3K3")
      (footprint "eagle-import:0207_12")
      (libsource (lib "eagle-import") (part "R-EU_0207/12"))
    )
    (comp (ref "R41")
      (value "680")
      (footprint "eagle-import:0207_5V")
      (libsource (lib "eagle-import") (part "R-EU_0207/5V"))
    )
    (comp (ref "R42")
      (value "100")
      (footprint "eagle-import:0207_5V")
      (libsource (lib "eagle-import") (part "R-EU_0207/5V"))
    )
    (comp (ref "R43")
      (value "2K2")
      (footprint "eagle-import:0207_12")
      (libsource (lib "eagle-import") (part "R-EU_0207/12"))
    )
    (comp (ref "R44")
      (value "2K2")
      (footprint "eagle-import:0207_12")
      (libsource (lib "eagle-import") (part "R-EU_0207/12"))
    )
    (comp (ref "R45")
      (value "470")
      (footprint "eagle-import:0207_12")
      (libsource (lib "eagle-import") (part "R-EU_0207/12"))
    )
    (comp (ref "R46")
      (value "10K")
      (footprint "eagle-import:0207_12")
      (libsource (lib "eagle-import") (part "R-EU_0207/12"))
    )
    (comp (ref "R47")
      (value "100")
      (footprint "eagle-import:0207_12")
      (libsource (lib "eagle-import") (part "R-EU_0207/12"))
    )
    (comp (ref "R48")
      (value "220")
      (footprint "eagle-import:0207_12")
      (libsource (lib "eagle-import") (part "R-EU_0207/12"))
    )
    (comp (ref "R49")
      (value "1K")
      (footprint "eagle-import:0207_12")
      (libsource (lib "eagle-import") (part "R-EU_0207/12"))
    )
    (comp (ref "R50")
      (value "1K")
      (footprint "eagle-import:0207_12")
      (libsource (lib "eagle-import") (part "R-EU_0207/12"))
    )
    (comp (ref "R51")
      (value "4K7")
      (footprint "eagle-import:0207_12")
      (libsource (lib "eagle-import") (part "R-EU_0207/12"))
    )
    (comp (ref "R53")
      (value "47K")
      (footprint "eagle-import:0207_12")
      (libsource (lib "eagle-import") (part "R-EU_0207/12"))
    )
    (comp (ref "R54")
      (value "39K")
      (footprint "eagle-import:0207_12")
      (libsource (lib "eagle-import") (part "R-EU_0207/12"))
    )
    (comp (ref "R55")
      (value "1K")
      (footprint "eagle-import:0207_5V")
      (libsource (lib "eagle-import") (part "R-EU_0207/5V"))
    )
    (comp (ref "R56")
      (value "1K")
      (footprint "eagle-import:0207_5V")
      (libsource (lib "eagle-import") (part "R-EU_0207/5V"))
    )
    (comp (ref "R57")
      (value "220")
      (footprint "eagle-import:0207_5V")
      (libsource (lib "eagle-import") (part "R-EU_0207/5V"))
    )
    (comp (ref "R58")
      (value "220")
      (footprint "eagle-import:0207_5V")
      (libsource (lib "eagle-import") (part "R-EU_0207/5V"))
    )
    (comp (ref "R59")
      (value "470")
      (footprint "eagle-import:0207_5V")
      (libsource (lib "eagle-import") (part "R-EU_0207/5V"))
    )
    (comp (ref "R63")
      (value "4K7")
      (footprint "eagle-import:0207_12")
      (libsource (lib "eagle-import") (part "R-EU_0207/12"))
    )
    (comp (ref "R64")
      (value "4K7")
      (footprint "eagle-import:0207_12")
      (libsource (lib "eagle-import") (part "R-EU_0207/12"))
    )
    (comp (ref "R65")
      (value "1K")
      (footprint "eagle-import:0207_12")
      (libsource (lib "eagle-import") (part "R-EU_0207/12"))
    )
    (comp (ref "R66")
      (value "470")
      (footprint "eagle-import:0207_12")
      (libsource (lib "eagle-import") (part "R-EU_0207/12"))
    )
    (comp (ref "R67")
      (value "470")
      (footprint "eagle-import:0207_12")
      (libsource (lib "eagle-import") (part "R-EU_0207/12"))
    )
    (comp (ref "R68")
      (value "100")
      (footprint "eagle-import:0207_12")
      (libsource (lib "eagle-import") (part "R-EU_0207/12"))
    )
    (comp (ref "R69")
      (value "100")
      (footprint "eagle-import:0207_5V")
      (libsource (lib "eagle-import") (part "R-EU_0207/5V"))
    )
    (comp (ref "R70")
      (value "100")
      (footprint "eagle-import:0207_5V")
      (libsource (lib "eagle-import") (part "R-EU_0207/5V"))
    )
    (comp (ref "R71")
      (value "3K3")
      (footprint "eagle-import:0207_5V")
      (libsource (lib "eagle-import") (part "R-EU_0207/5V"))
    )
    (comp (ref "R72")
      (value "10K")
      (footprint "eagle-import:0207_5V")
      (libsource (lib "eagle-import") (part "R-EU_0207/5V"))
    )
    (comp (ref "R73")
      (value "10K")
      (footprint "eagle-import:0207_5V")
      (libsource (lib "eagle-import") (part "R-EU_0207/5V"))
    )
    (comp (ref "R73_")
      (value "3K3")
      (footprint "eagle-import:0207_12")
      (libsource (lib "eagle-import") (part "R-EU_0207/12"))
    )
    (comp (ref "R74")
      (value "10K")
      (footprint "eagle-import:0207_5V")
      (libsource (lib "eagle-import") (part "R-EU_0207/5V"))
    )
    (comp (ref "R74_")
      (value "470")
      (footprint "eagle-import:0207_12")
      (libsource (lib "eagle-import") (part "R-EU_0207/12"))
    )
    (comp (ref "R75")
      (value "10K")
      (footprint "eagle-import:0207_12")
      (libsource (lib "eagle-import") (part "R-EU_0207/12"))
    )
    (comp (ref "R76")
      (value "150")
      (footprint "eagle-import:0207_5V")
      (libsource (lib "eagle-import") (part "R-EU_0207/5V"))
    )
    (comp (ref "R77")
      (value "75")
      (footprint "eagle-import:0207_5V")
      (libsource (lib "eagle-import") (part "R-EU_0207/5V"))
    )
    (comp (ref "TP1")
      (value "TPSQPAD1-13")
      (footprint "eagle-import:P1-13")
      (libsource (lib "eagle-import") (part "TPSQPAD1-13"))
    )
    (comp (ref "TP2")
      (value "TPSQPAD1-13")
      (footprint "eagle-import:P1-13")
      (libsource (lib "eagle-import") (part "TPSQPAD1-13"))
    )
    (comp (ref "TP3")
      (value "TPSQPAD1-13")
      (footprint "eagle-import:P1-13")
      (libsource (lib "eagle-import") (part "TPSQPAD1-13"))
    )
    (comp (ref "TP4")
      (value "TPSQPAD1-13")
      (footprint "eagle-import:P1-13")
      (libsource (lib "eagle-import") (part "TPSQPAD1-13"))
    )
    (comp (ref "TP5")
      (value "TPSQPAD1-13")
      (footprint "eagle-import:P1-13")
      (libsource (lib "eagle-import") (part "TPSQPAD1-13"))
    )
    (comp (ref "TP6")
      (value "TPSQPAD1-13")
      (footprint "eagle-import:P1-13")
      (libsource (lib "eagle-import") (part "TPSQPAD1-13"))
    )
    (comp (ref "TP7")
      (value "TPSQPAD1-13")
      (footprint "eagle-import:P1-13")
      (libsource (lib "eagle-import") (part "TPSQPAD1-13"))
    )
    (comp (ref "TP8")
      (value "TPSQPAD1-13")
      (footprint "eagle-import:P1-13")
      (libsource (lib "eagle-import") (part "TPSQPAD1-13"))
    )
    (comp (ref "TP9")
      (value "TPSQPAD1-13")
      (footprint "eagle-import:P1-13")
      (libsource (lib "eagle-import") (part "TPSQPAD1-13"))
    )
    (comp (ref "TP10")
      (value "TPSQPAD1-13")
      (footprint "eagle-import:P1-13")
      (libsource (lib "eagle-import") (part "TPSQPAD1-13"))
    )
    (comp (ref "U$1")
      (value "TK90_EDGE")
      (footprint "eagle-import:TK-EDGE")
      (libsource (lib "eagle-import") (part "TK90_EDGE"))
    )
    (comp (ref "X1")
      (value "RCA2PINA1")
      (footprint "eagle-import:TOBU3")
      (fields (field (name "MF") "FARNELL") (field (name "MPN") "TOBU 3"))
      (libsource (lib "eagle-import") (part "RCA2PINA1"))
    )
    (comp (ref "X2")
      (value "POWER")
      (footprint "eagle-import:MONO")
      (libsource (lib "eagle-import") (part "JACK?-MONO"))
    )
    (comp (ref "XTAL")
      (value "14.3044MHz")
      (footprint "eagle-import:HC49_S")
      (libsource (lib "eagle-import") (part "CRYSTALHC49S"))
    )
  )
  (nets
    (net (code "1") (name "+5V") (class "Default")
      (node (ref "7805") (pin "OUT") (pinfunction "OUT_OUT") (pintype "passive"))
      (node (ref "C1") (pin "+") (pinfunction "+_+") (pintype "passive"))
      (node (ref "C12") (pin "2") (pinfunction "2_2") (pintype "passive"))
      (node (ref "C13") (pin "2") (pinfunction "2_2") (pintype "passive"))
      (node (ref "C14") (pin "2") (pinfunction "2_2") (pintype "passive"))
      (node (ref "C15") (pin "1") (pinfunction "1_1") (pintype "passive"))
      (node (ref "C16") (pin "1") (pinfunction "1_1") (pintype "passive"))
      (node (ref "C18") (pin "1") (pinfunction "1_1") (pintype "passive"))
      (node (ref "C19") (pin "1") (pinfunction "1_1") (pintype "passive"))
      (node (ref "C20") (pin "1") (pinfunction "1_1") (pintype "passive"))
      (node (ref "C21") (pin "1") (pinfunction "1_1") (pintype "passive"))
      (node (ref "C22") (pin "2") (pinfunction "2_2") (pintype "passive"))
      (node (ref "C24") (pin "2") (pinfunction "2_2") (pintype "passive"))
      (node (ref "C29") (pin "2") (pinfunction "2_2") (pintype "passive"))
      (node (ref "C31") (pin "2") (pinfunction "2_2") (pintype "passive"))
      (node (ref "C32") (pin "2") (pinfunction "2_2") (pintype "passive"))
      (node (ref "C33") (pin "2") (pinfunction "2_2") (pintype "passive"))
      (node (ref "D13") (pin "C") (pinfunction "K_C") (pintype "bidirectional"))
      (node (ref "D15") (pin "C") (pinfunction "K_C") (pintype "bidirectional"))
      (node (ref "D17") (pin "C") (pinfunction "K_C") (pintype "bidirectional"))
      (node (ref "IC1") (pin "11") (pinfunction "VCC_11") (pintype "power_in"))
      (node (ref "IC10") (pin "16") (pinfunction "VCC_16") (pintype "power_in"))
      (node (ref "IC11") (pin "20") (pinfunction "VCC_20") (pintype "power_in"))
      (node (ref "IC12") (pin "3") (pinfunction "CR_BIAS_3") (pintype "input"))
      (node (ref "IC13") (pin "9") (pinfunction "A7_9") (pintype "input"))
      (node (ref "IC14") (pin "9") (pinfunction "A7_9") (pintype "input"))
      (node (ref "IC15") (pin "9") (pinfunction "A7_9") (pintype "input"))
      (node (ref "IC16") (pin "9") (pinfunction "A7_9") (pintype "input"))
      (node (ref "IC17") (pin "9") (pinfunction "A7_9") (pintype "input"))
      (node (ref "IC18") (pin "9") (pinfunction "A7_9") (pintype "input"))
      (node (ref "IC19") (pin "9") (pinfunction "A7_9") (pintype "input"))
      (node (ref "IC2") (pin "1") (pinfunction "VPP_1") (pintype "input"))
      (node (ref "IC2") (pin "28") (pinfunction "VCC_28") (pintype "power_in"))
      (node (ref "IC20") (pin "9") (pinfunction "A7_9") (pintype "input"))
      (node (ref "IC21") (pin "9") (pinfunction "VCC_9") (pintype "power_in"))
      (node (ref "IC22") (pin "9") (pinfunction "VCC_9") (pintype "power_in"))
      (node (ref "IC23") (pin "9") (pinfunction "VCC_9") (pintype "power_in"))
      (node (ref "IC24") (pin "9") (pinfunction "VCC_9") (pintype "power_in"))
      (node (ref "IC25") (pin "14") (pinfunction "VCC_14") (pintype "power_in"))
      (node (ref "IC26") (pin "1") (pinfunction "I0_1") (pintype "input"))
      (node (ref "IC26") (pin "14") (pinfunction "VCC_14") (pintype "power_in"))
      (node (ref "IC27") (pin "14") (pinfunction "VCC_14") (pintype "power_in"))
      (node (ref "IC28") (pin "14") (pinfunction "VCC_14") (pintype "power_in"))
      (node (ref "IC3") (pin "40") (pinfunction "VCC_40") (pintype "power_in"))
      (node (ref "IC4") (pin "10") (pinfunction "PRE_10") (pintype "input"))
      (node (ref "IC4") (pin "13") (pinfunction "CLR_13") (pintype "input"))
      (node (ref "IC4") (pin "14") (pinfunction "VCC_14") (pintype "power_in"))
      (node (ref "IC5") (pin "1") (pinfunction "CLR_1") (pintype "input"))
      (node (ref "IC5") (pin "10") (pinfunction "PRE_10") (pintype "input"))
      (node (ref "IC5") (pin "13") (pinfunction "CLR_13") (pintype "input"))
      (node (ref "IC5") (pin "14") (pinfunction "VCC_14") (pintype "power_in"))
      (node (ref "IC5") (pin "4") (pinfunction "PRE_4") (pintype "input"))
      (node (ref "IC6") (pin "16") (pinfunction "VCC_16") (pintype "power_in"))
      (node (ref "IC7") (pin "16") (pinfunction "VCC_16") (pintype "power_in"))
      (node (ref "IC8") (pin "16") (pinfunction "VCC_16") (pintype "power_in"))
      (node (ref "IC9") (pin "16") (pinfunction "VCC_16") (pintype "power_in"))
      (node (ref "J1") (pin "1") (pinfunction "1_1") (pintype "passive"))
      (node (ref "J2") (pin "1") (pinfunction "1_1") (pintype "passive"))
      (node (ref "Q1") (pin "3") (pinfunction "C_3") (pintype "passive"))
      (node (ref "R17") (pin "2") (pinfunction "2_2") (pintype "passive"))
      (node (ref "R18") (pin "2") (pinfunction "2_2") (pintype "passive"))
      (node (ref "R19") (pin "2") (pinfunction "2_2") (pintype "passive"))
      (node (ref "R20") (pin "2") (pinfunction "2_2") (pintype "passive"))
      (node (ref "R21") (pin "2") (pinfunction "2_2") (pintype "passive"))
      (node (ref "R22") (pin "2") (pinfunction "2_2") (pintype "passive"))
      (node (ref "R23") (pin "2") (pinfunction "2_2") (pintype "passive"))
      (node (ref "R24") (pin "2") (pinfunction "2_2") (pintype "passive"))
      (node (ref "R29") (pin "2") (pinfunction "2_2") (pintype "passive"))
      (node (ref "R30") (pin "1") (pinfunction "1_1") (pintype "passive"))
      (node (ref "R31") (pin "1") (pinfunction "1_1") (pintype "passive"))
      (node (ref "R32") (pin "1") (pinfunction "1_1") (pintype "passive"))
      (node (ref "R35") (pin "1") (pinfunction "1_1") (pintype "passive"))
      (node (ref "R36") (pin "1") (pinfunction "1_1") (pintype "passive"))
      (node (ref "R37") (pin "1") (pinfunction "1_1") (pintype "passive"))
      (node (ref "R38") (pin "1") (pinfunction "1_1") (pintype "passive"))
      (node (ref "R39") (pin "1") (pinfunction "1_1") (pintype "passive"))
      (node (ref "R40") (pin "2") (pinfunction "2_2") (pintype "passive"))
      (node (ref "R43") (pin "2") (pinfunction "2_2") (pintype "passive"))
      (node (ref "R48") (pin "2") (pinfunction "2_2") (pintype "passive"))
      (node (ref "R51") (pin "2") (pinfunction "2_2") (pintype "passive"))
      (node (ref "R74_") (pin "2") (pinfunction "2_2") (pintype "passive"))
      (node (ref "U$1") (pin "3A") (pinfunction "EDGE_3A") (pintype "bidirectional"))
    )
    (net (code "2") (name "+12V") (class "Default")
      (node (ref "C43") (pin "2") (pinfunction "2_2") (pintype "passive"))
      (node (ref "C53") (pin "+") (pinfunction "+_+") (pintype "passive"))
      (node (ref "D24") (pin "C") (pinfunction "K_C") (pintype "bidirectional"))
      (node (ref "IC11") (pin "5") (pinfunction "+12V_5") (pintype "power_in"))
      (node (ref "IC12") (pin "14") (pinfunction "RFVCC_14") (pintype "power_in"))
      (node (ref "IC12") (pin "16") (pinfunction "CRVCC_16") (pintype "power_in"))
      (node (ref "L1") (pin "2") (pinfunction "A_2") (pintype "passive"))
      (node (ref "Q8") (pin "3") (pinfunction "C_3") (pintype "passive"))
      (node (ref "R54") (pin "1") (pinfunction "1_1") (pintype "passive"))
      (node (ref "R57") (pin "1") (pinfunction "1_1") (pintype "passive"))
      (node (ref "R58") (pin "1") (pinfunction "1_1") (pintype "passive"))
      (node (ref "R59") (pin "1") (pinfunction "1_1") (pintype "passive"))
      (node (ref "R68") (pin "1") (pinfunction "1_1") (pintype "passive"))
      (node (ref "U$1") (pin "22B") (pinfunction "EDGE_22B") (pintype "bidirectional"))
    )
    (net (code "3") (name "-5V") (class "Default")
      (node (ref "C50") (pin "1") (pinfunction "1_1") (pintype "passive"))
      (node (ref "D21") (pin "A") (pinfunction "A_A") (pintype "bidirectional"))
      (node (ref "J3") (pin "1") (pinfunction "1_1") (pintype "passive"))
      (node (ref "R67") (pin "1") (pinfunction "1_1") (pintype "passive"))
      (node (ref "U$1") (pin "20B") (pinfunction "EDGE_20B") (pintype "bidirectional"))
    )
    (net (code "4") (name "/+12V_UNREG") (class "Default")
      (node (ref "C48") (pin "1") (pinfunction "1_1") (pintype "passive"))
      (node (ref "C51") (pin "1") (pinfunction "1_1") (pintype "passive"))
      (node (ref "Q5") (pin "E") (pinfunction "E_E") (pintype "passive"))
      (node (ref "Q6") (pin "E") (pinfunction "E_E") (pintype "passive"))
      (node (ref "U$1") (pin "23B") (pinfunction "EDGE_23B") (pintype "bidirectional"))
    )
    (net (code "5") (name "/A0") (class "Default")
      (node (ref "IC1") (pin "30") (pinfunction "A0_30") (pintype "output"))
      (node (ref "IC2") (pin "10") (pinfunction "A0_10") (pintype "input"))
      (node (ref "IC7") (pin "3") (pinfunction "1B_3") (pintype "input"))
      (node (ref "IC8") (pin "3") (pinfunction "1B_3") (pintype "input"))
      (node (ref "Q1") (pin "2") (pinfunction "B_2") (pintype "passive"))
      (node (ref "U$1") (pin "9A") (pinfunction "EDGE_9A") (pintype "bidirectional"))
    )
    (net (code "6") (name "/A1") (class "Default")
      (node (ref "IC1") (pin "31") (pinfunction "A1_31") (pintype "output"))
      (node (ref "IC2") (pin "9") (pinfunction "A1_9") (pintype "input"))
      (node (ref "IC7") (pin "6") (pinfunction "2B_6") (pintype "input"))
      (node (ref "IC8") (pin "6") (pinfunction "2B_6") (pintype "input"))
      (node (ref "U$1") (pin "10A") (pinfunction "EDGE_10A") (pintype "bidirectional"))
    )
    (net (code "7") (name "/A2") (class "Default")
      (node (ref "IC1") (pin "32") (pinfunction "A2_32") (pintype "output"))
      (node (ref "IC2") (pin "8") (pinfunction "A2_8") (pintype "input"))
      (node (ref "IC7") (pin "13") (pinfunction "4B_13") (pintype "input"))
      (node (ref "IC8") (pin "13") (pinfunction "4B_13") (pintype "input"))
      (node (ref "U$1") (pin "11A") (pinfunction "EDGE_11A") (pintype "bidirectional"))
    )
    (net (code "8") (name "/A3") (class "Default")
      (node (ref "IC1") (pin "33") (pinfunction "A3_33") (pintype "output"))
      (node (ref "IC2") (pin "7") (pinfunction "A3_7") (pintype "input"))
      (node (ref "IC7") (pin "10") (pinfunction "3B_10") (pintype "input"))
      (node (ref "IC8") (pin "10") (pinfunction "3B_10") (pintype "input"))
      (node (ref "U$1") (pin "12A") (pinfunction "EDGE_12A") (pintype "bidirectional"))
    )
    (net (code "9") (name "/A4") (class "Default")
      (node (ref "IC1") (pin "34") (pinfunction "A4_34") (pintype "output"))
      (node (ref "IC2") (pin "6") (pinfunction "A4_6") (pintype "input"))
      (node (ref "IC6") (pin "6") (pinfunction "2B_6") (pintype "input"))
      (node (ref "IC9") (pin "6") (pinfunction "2B_6") (pintype "input"))
      (node (ref "U$1") (pin "24A") (pinfunction "EDGE_24A") (pintype "bidirectional"))
    )
    (net (code "10") (name "/A5") (class "Default")
      (node (ref "IC1") (pin "35") (pinfunction "A5_35") (pintype "output"))
      (node (ref "IC2") (pin "5") (pinfunction "A5_5") (pintype "input"))
      (node (ref "IC6") (pin "13") (pinfunction "4B_13") (pintype "input"))
      (node (ref "IC9") (pin "13") (pinfunction "4B_13") (pintype "input"))
      (node (ref "U$1") (pin "23A") (pinfunction "EDGE_23A") (pintype "bidirectional"))
    )
    (net (code "11") (name "/A6") (class "Default")
      (node (ref "IC1") (pin "36") (pinfunction "A6_36") (pintype "output"))
      (node (ref "IC2") (pin "4") (pinfunction "A6_4") (pintype "input"))
      (node (ref "IC21") (pin "14") (pinfunction "A0_14") (pintype "input"))
      (node (ref "IC22") (pin "14") (pinfunction "A0_14") (pintype "input"))
      (node (ref "IC23") (pin "14") (pinfunction "A0_14") (pintype "input"))
      (node (ref "IC24") (pin "14") (pinfunction "A0_14") (pintype "input"))
      (node (ref "IC5") (pin "12") (pinfunction "D_12") (pintype "input"))
      (node (ref "IC9") (pin "10") (pinfunction "3B_10") (pintype "input"))
      (node (ref "U$1") (pin "22A") (pinfunction "EDGE_22A") (pintype "bidirectional"))
    )
    (net (code "12") (name "/A7") (class "Default")
      (node (ref "IC1") (pin "37") (pinfunction "A7_37") (pintype "output"))
      (node (ref "IC2") (pin "3") (pinfunction "A7_3") (pintype "input"))
      (node (ref "IC26") (pin "12") (pinfunction "I0_12") (pintype "input"))
      (node (ref "IC8") (pin "2") (pinfunction "1A_2") (pintype "input"))
      (node (ref "U$1") (pin "21A") (pinfunction "EDGE_21A") (pintype "bidirectional"))
    )
    (net (code "13") (name "/A7'") (class "Default")
      (node (ref "IC21") (pin "10") (pinfunction "A7_10") (pintype "input"))
      (node (ref "IC22") (pin "10") (pinfunction "A7_10") (pintype "input"))
      (node (ref "IC23") (pin "10") (pinfunction "A7_10") (pintype "input"))
      (node (ref "IC24") (pin "10") (pinfunction "A7_10") (pintype "input"))
      (node (ref "IC26") (pin "8") (pinfunction "O_8") (pintype "output"))
    )
    (net (code "14") (name "/A8") (class "Default")
      (node (ref "D2") (pin "C") (pinfunction "K_C") (pintype "bidirectional"))
      (node (ref "IC1") (pin "38") (pinfunction "A8_38") (pintype "output"))
      (node (ref "IC2") (pin "25") (pinfunction "A8_25") (pintype "input"))
      (node (ref "IC7") (pin "5") (pinfunction "2A_5") (pintype "input"))
      (node (ref "IC8") (pin "5") (pinfunction "2A_5") (pintype "input"))
      (node (ref "U$1") (pin "26B") (pinfunction "EDGE_26B") (pintype "bidirectional"))
    )
    (net (code "15") (name "/A8-1") (class "Default")
      (node (ref "IC21") (pin "7") (pinfunction "A5_7") (pintype "input"))
      (node (ref "IC22") (pin "7") (pinfunction "A5_7") (pintype "input"))
      (node (ref "IC23") (pin "7") (pinfunction "A5_7") (pintype "input"))
      (node (ref "IC24") (pin "7") (pinfunction "A5_7") (pintype "input"))
      (node (ref "IC7") (pin "7") (pinfunction "2Y_7") (pintype "output"))
    )
    (net (code "16") (name "/A9") (class "Default")
      (node (ref "D3") (pin "C") (pinfunction "K_C") (pintype "bidirectional"))
      (node (ref "IC1") (pin "39") (pinfunction "A9_39") (pintype "output"))
      (node (ref "IC2") (pin "24") (pinfunction "A9_24") (pintype "input"))
      (node (ref "IC7") (pin "14") (pinfunction "4A_14") (pintype "input"))
      (node (ref "IC8") (pin "14") (pinfunction "4A_14") (pintype "input"))
      (node (ref "U$1") (pin "27A") (pinfunction "EDGE_27A") (pintype "bidirectional"))
    )
    (net (code "17") (name "/A9-2") (class "Default")
      (node (ref "IC21") (pin "8") (pinfunction "A4_8") (pintype "input"))
      (node (ref "IC22") (pin "8") (pinfunction "A4_8") (pintype "input"))
      (node (ref "IC23") (pin "8") (pinfunction "A4_8") (pintype "input"))
      (node (ref "IC24") (pin "8") (pinfunction "A4_8") (pintype "input"))
      (node (ref "IC7") (pin "12") (pinfunction "4Y_12") (pintype "output"))
    )
    (net (code "18") (name "/A10") (class "Default")
      (node (ref "D4") (pin "C") (pinfunction "K_C") (pintype "bidirectional"))
      (node (ref "IC1") (pin "40") (pinfunction "A10_40") (pintype "output"))
      (node (ref "IC2") (pin "21") (pinfunction "A10_21") (pintype "input"))
      (node (ref "IC7") (pin "11") (pinfunction "3A_11") (pintype "input"))
      (node (ref "IC8") (pin "11") (pinfunction "3A_11") (pintype "input"))
      (node (ref "U$1") (pin "27B") (pinfunction "EDGE_27B") (pintype "bidirectional"))
    )
    (net (code "19") (name "/A10-3") (class "Default")
      (node (ref "IC21") (pin "11") (pinfunction "A3_11") (pintype "input"))
      (node (ref "IC22") (pin "11") (pinfunction "A3_11") (pintype "input"))
      (node (ref "IC23") (pin "11") (pinfunction "A3_11") (pintype "input"))
      (node (ref "IC24") (pin "11") (pinfunction "A3_11") (pintype "input"))
      (node (ref "IC7") (pin "9") (pinfunction "3Y_9") (pintype "output"))
    )
    (net (code "20") (name "/A11") (class "Default")
      (node (ref "D5") (pin "C") (pinfunction "K_C") (pintype "bidirectional"))
      (node (ref "IC1") (pin "1") (pinfunction "A11_1") (pintype "output"))
      (node (ref "IC2") (pin "23") (pinfunction "A11_23") (pintype "input"))
      (node (ref "IC6") (pin "5") (pinfunction "2A_5") (pintype "input"))
      (node (ref "IC9") (pin "5") (pinfunction "2A_5") (pintype "input"))
      (node (ref "U$1") (pin "28A") (pinfunction "EDGE_28A") (pintype "bidirectional"))
    )
    (net (code "21") (name "/A11-4") (class "Default")
      (node (ref "IC21") (pin "12") (pinfunction "A2_12") (pintype "input"))
      (node (ref "IC22") (pin "12") (pinfunction "A2_12") (pintype "input"))
      (node (ref "IC23") (pin "12") (pinfunction "A2_12") (pintype "input"))
      (node (ref "IC24") (pin "12") (pinfunction "A2_12") (pintype "input"))
      (node (ref "IC6") (pin "7") (pinfunction "2Y_7") (pintype "output"))
    )
    (net (code "22") (name "/A12") (class "Default")
      (node (ref "D6") (pin "C") (pinfunction "K_C") (pintype "bidirectional"))
      (node (ref "IC1") (pin "2") (pinfunction "A12_2") (pintype "output"))
      (node (ref "IC2") (pin "2") (pinfunction "A12_2") (pintype "input"))
      (node (ref "IC6") (pin "14") (pinfunction "4A_14") (pintype "input"))
      (node (ref "IC9") (pin "14") (pinfunction "4A_14") (pintype "input"))
      (node (ref "U$1") (pin "2A") (pinfunction "EDGE_2A") (pintype "bidirectional"))
    )
    (net (code "23") (name "/A12-5") (class "Default")
      (node (ref "IC21") (pin "13") (pinfunction "A1_13") (pintype "input"))
      (node (ref "IC22") (pin "13") (pinfunction "A1_13") (pintype "input"))
      (node (ref "IC23") (pin "13") (pinfunction "A1_13") (pintype "input"))
      (node (ref "IC24") (pin "13") (pinfunction "A1_13") (pintype "input"))
      (node (ref "IC6") (pin "12") (pinfunction "4Y_12") (pintype "output"))
    )
    (net (code "24") (name "/A13") (class "Default")
      (node (ref "D7") (pin "C") (pinfunction "K_C") (pintype "bidirectional"))
      (node (ref "IC1") (pin "3") (pinfunction "A13_3") (pintype "output"))
      (node (ref "IC2") (pin "26") (pinfunction "A13_26") (pintype "input"))
      (node (ref "IC7") (pin "2") (pinfunction "1A_2") (pintype "input"))
      (node (ref "IC9") (pin "11") (pinfunction "3A_11") (pintype "input"))
      (node (ref "U$1") (pin "2B") (pinfunction "EDGE_2B") (pintype "bidirectional"))
    )
    (net (code "25") (name "/A13-0") (class "Default")
      (node (ref "IC21") (pin "6") (pinfunction "A6_6") (pintype "input"))
      (node (ref "IC22") (pin "6") (pinfunction "A6_6") (pintype "input"))
      (node (ref "IC23") (pin "6") (pinfunction "A6_6") (pintype "input"))
      (node (ref "IC24") (pin "6") (pinfunction "A6_6") (pintype "input"))
      (node (ref "IC7") (pin "4") (pinfunction "1Y_4") (pintype "output"))
    )
    (net (code "26") (name "/A14") (class "Default")
      (node (ref "D12") (pin "A") (pinfunction "A_A") (pintype "bidirectional"))
      (node (ref "D8") (pin "C") (pinfunction "K_C") (pintype "bidirectional"))
      (node (ref "IC1") (pin "4") (pinfunction "A14_4") (pintype "output"))
      (node (ref "IC25") (pin "4") (pinfunction "I0_4") (pintype "input"))
      (node (ref "IC27") (pin "12") (pinfunction "I0_12") (pintype "input"))
      (node (ref "IC28") (pin "1") (pinfunction "I_1") (pintype "input"))
      (node (ref "IC3") (pin "37") (pinfunction "A14_37") (pintype "input"))
      (node (ref "U$1") (pin "1A") (pinfunction "EDGE_1A") (pintype "bidirectional"))
    )
    (net (code "27") (name "/A15") (class "Default")
      (node (ref "D11") (pin "A") (pinfunction "A_A") (pintype "bidirectional"))
      (node (ref "D9") (pin "C") (pinfunction "K_C") (pintype "bidirectional"))
      (node (ref "IC1") (pin "5") (pinfunction "A15_5") (pintype "output"))
      (node (ref "IC25") (pin "13") (pinfunction "I1_13") (pintype "input"))
      (node (ref "IC27") (pin "13") (pinfunction "I1_13") (pintype "input"))
      (node (ref "IC3") (pin "38") (pinfunction "A15_38") (pintype "input"))
      (node (ref "U$1") (pin "1B") (pinfunction "EDGE_1B") (pintype "bidirectional"))
    )
    (net (code "28") (name "/AA0") (class "Default")
      (node (ref "IC13") (pin "5") (pinfunction "A0_5") (pintype "input"))
      (node (ref "IC14") (pin "5") (pinfunction "A0_5") (pintype "input"))
      (node (ref "IC15") (pin "5") (pinfunction "A0_5") (pintype "input"))
      (node (ref "IC16") (pin "5") (pinfunction "A0_5") (pintype "input"))
      (node (ref "IC17") (pin "5") (pinfunction "A0_5") (pintype "input"))
      (node (ref "IC18") (pin "5") (pinfunction "A0_5") (pintype "input"))
      (node (ref "IC19") (pin "5") (pinfunction "A0_5") (pintype "input"))
      (node (ref "IC20") (pin "5") (pinfunction "A0_5") (pintype "input"))
      (node (ref "IC3") (pin "9") (pinfunction "A0_9") (pintype "output"))
      (node (ref "R9") (pin "1") (pinfunction "1_1") (pintype "passive"))
    )
    (net (code "29") (name "/AA1") (class "Default")
      (node (ref "IC13") (pin "7") (pinfunction "A1_7") (pintype "input"))
      (node (ref "IC14") (pin "7") (pinfunction "A1_7") (pintype "input"))
      (node (ref "IC15") (pin "7") (pinfunction "A1_7") (pintype "input"))
      (node (ref "IC16") (pin "7") (pinfunction "A1_7") (pintype "input"))
      (node (ref "IC17") (pin "7") (pinfunction "A1_7") (pintype "input"))
      (node (ref "IC18") (pin "7") (pinfunction "A1_7") (pintype "input"))
      (node (ref "IC19") (pin "7") (pinfunction "A1_7") (pintype "input"))
      (node (ref "IC20") (pin "7") (pinfunction "A1_7") (pintype "input"))
      (node (ref "IC3") (pin "7") (pinfunction "A1_7") (pintype "output"))
      (node (ref "R11") (pin "1") (pinfunction "1_1") (pintype "passive"))
    )
    (net (code "30") (name "/AA2") (class "Default")
      (node (ref "IC13") (pin "6") (pinfunction "A2_6") (pintype "input"))
      (node (ref "IC14") (pin "6") (pinfunction "A2_6") (pintype "input"))
      (node (ref "IC15") (pin "6") (pinfunction "A2_6") (pintype "input"))
      (node (ref "IC16") (pin "6") (pinfunction "A2_6") (pintype "input"))
      (node (ref "IC17") (pin "6") (pinfunction "A2_6") (pintype "input"))
      (node (ref "IC18") (pin "6") (pinfunction "A2_6") (pintype "input"))
      (node (ref "IC19") (pin "6") (pinfunction "A2_6") (pintype "input"))
      (node (ref "IC20") (pin "6") (pinfunction "A2_6") (pintype "input"))
      (node (ref "IC3") (pin "8") (pinfunction "A2_8") (pintype "output"))
      (node (ref "R10") (pin "1") (pinfunction "1_1") (pintype "passive"))
    )
    (net (code "31") (name "/AA3") (class "Default")
      (node (ref "IC13") (pin "12") (pinfunction "A3_12") (pintype "input"))
      (node (ref "IC14") (pin "12") (pinfunction "A3_12") (pintype "input"))
      (node (ref "IC15") (pin "12") (pinfunction "A3_12") (pintype "input"))
      (node (ref "IC16") (pin "12") (pinfunction "A3_12") (pintype "input"))
      (node (ref "IC17") (pin "12") (pinfunction "A3_12") (pintype "input"))
      (node (ref "IC18") (pin "12") (pinfunction "A3_12") (pintype "input"))
      (node (ref "IC19") (pin "12") (pinfunction "A3_12") (pintype "input"))
      (node (ref "IC20") (pin "12") (pinfunction "A3_12") (pintype "input"))
      (node (ref "IC3") (pin "4") (pinfunction "A3_4") (pintype "output"))
      (node (ref "R14") (pin "1") (pinfunction "1_1") (pintype "passive"))
    )
    (net (code "32") (name "/AA4") (class "Default")
      (node (ref "IC13") (pin "11") (pinfunction "A4_11") (pintype "input"))
      (node (ref "IC14") (pin "11") (pinfunction "A4_11") (pintype "input"))
      (node (ref "IC15") (pin "11") (pinfunction "A4_11") (pintype "input"))
      (node (ref "IC16") (pin "11") (pinfunction "A4_11") (pintype "input"))
      (node (ref "IC17") (pin "11") (pinfunction "A4_11") (pintype "input"))
      (node (ref "IC18") (pin "11") (pinfunction "A4_11") (pintype "input"))
      (node (ref "IC19") (pin "11") (pinfunction "A4_11") (pintype "input"))
      (node (ref "IC20") (pin "11") (pinfunction "A4_11") (pintype "input"))
      (node (ref "IC3") (pin "5") (pinfunction "A4_5") (pintype "output"))
      (node (ref "R13") (pin "1") (pinfunction "1_1") (pintype "passive"))
    )
    (net (code "33") (name "/AA5") (class "Default")
      (node (ref "IC13") (pin "10") (pinfunction "A5_10") (pintype "input"))
      (node (ref "IC14") (pin "10") (pinfunction "A5_10") (pintype "input"))
      (node (ref "IC15") (pin "10") (pinfunction "A5_10") (pintype "input"))
      (node (ref "IC16") (pin "10") (pinfunction "A5_10") (pintype "input"))
      (node (ref "IC17") (pin "10") (pinfunction "A5_10") (pintype "input"))
      (node (ref "IC18") (pin "10") (pinfunction "A5_10") (pintype "input"))
      (node (ref "IC19") (pin "10") (pinfunction "A5_10") (pintype "input"))
      (node (ref "IC20") (pin "10") (pinfunction "A5_10") (pintype "input"))
      (node (ref "IC3") (pin "6") (pinfunction "A5_6") (pintype "output"))
      (node (ref "R12") (pin "1") (pinfunction "1_1") (pintype "passive"))
    )
    (net (code "34") (name "/AA6") (class "Default")
      (node (ref "IC13") (pin "13") (pinfunction "A6_13") (pintype "input"))
      (node (ref "IC14") (pin "13") (pinfunction "A6_13") (pintype "input"))
      (node (ref "IC15") (pin "13") (pinfunction "A6_13") (pintype "input"))
      (node (ref "IC16") (pin "13") (pinfunction "A6_13") (pintype "input"))
      (node (ref "IC17") (pin "13") (pinfunction "A6_13") (pintype "input"))
      (node (ref "IC18") (pin "13") (pinfunction "A6_13") (pintype "input"))
      (node (ref "IC19") (pin "13") (pinfunction "A6_13") (pintype "input"))
      (node (ref "IC20") (pin "13") (pinfunction "A6_13") (pintype "input"))
      (node (ref "IC3") (pin "3") (pinfunction "A6_3") (pintype "output"))
      (node (ref "R15") (pin "1") (pinfunction "1_1") (pintype "passive"))
    )
    (net (code "35") (name "/CARRIER") (class "Default")
      (node (ref "C47") (pin "1") (pinfunction "1_1") (pintype "passive"))
      (node (ref "D17") (pin "A") (pinfunction "A_A") (pintype "bidirectional"))
      (node (ref "D18") (pin "C") (pinfunction "K_C") (pintype "bidirectional"))
      (node (ref "IC3") (pin "39") (pinfunction "CARRIER_39") (pintype "output"))
      (node (ref "R64") (pin "2") (pinfunction "2_2") (pintype "passive"))
      (node (ref "R71") (pin "2") (pinfunction "2_2") (pintype "passive"))
    )
    (net (code "36") (name "/CLK") (class "Default")
      (node (ref "C9") (pin "2") (pinfunction "2_2") (pintype "passive"))
      (node (ref "IC3") (pin "36") (pinfunction "CKOUT_36") (pintype "output"))
      (node (ref "R49") (pin "2") (pinfunction "2_2") (pintype "passive"))
      (node (ref "R51") (pin "1") (pinfunction "1_1") (pintype "passive"))
      (node (ref "U$1") (pin "8A") (pinfunction "EDGE_8A") (pintype "bidirectional"))
    )
    (net (code "37") (name "/D0") (class "Default")
      (node (ref "IC1") (pin "14") (pinfunction "D0_14") (pintype "bidirectional"))
      (node (ref "IC10") (pin "3") (pinfunction "Y1_3") (pintype "tri_state"))
      (node (ref "IC2") (pin "11") (pinfunction "O0_11") (pintype "tri_state"))
      (node (ref "IC21") (pin "2") (pinfunction "I/O1_2") (pintype "bidirectional"))
      (node (ref "IC23") (pin "2") (pinfunction "I/O1_2") (pintype "bidirectional"))
      (node (ref "R1") (pin "2") (pinfunction "2_2") (pintype "passive"))
      (node (ref "R17") (pin "1") (pinfunction "1_1") (pintype "passive"))
      (node (ref "U$1") (pin "6B") (pinfunction "EDGE_6B") (pintype "bidirectional"))
    )
    (net (code "38") (name "/D0'") (class "Default")
      (node (ref "IC20") (pin "14") (pinfunction "DO_14") (pintype "bidirectional"))
      (node (ref "IC20") (pin "2") (pinfunction "DI_2") (pintype "bidirectional"))
      (node (ref "IC3") (pin "25") (pinfunction "D0_25") (pintype "bidirectional"))
      (node (ref "R1") (pin "1") (pinfunction "1_1") (pintype "passive"))
    )
    (net (code "39") (name "/D1") (class "Default")
      (node (ref "IC1") (pin "15") (pinfunction "D1_15") (pintype "bidirectional"))
      (node (ref "IC10") (pin "5") (pinfunction "Y2_5") (pintype "tri_state"))
      (node (ref "IC2") (pin "12") (pinfunction "O1_12") (pintype "tri_state"))
      (node (ref "IC21") (pin "3") (pinfunction "I/O2_3") (pintype "bidirectional"))
      (node (ref "IC23") (pin "3") (pinfunction "I/O2_3") (pintype "bidirectional"))
      (node (ref "R18") (pin "1") (pinfunction "1_1") (pintype "passive"))
      (node (ref "R2") (pin "2") (pinfunction "2_2") (pintype "passive"))
      (node (ref "U$1") (pin "7B") (pinfunction "EDGE_7B") (pintype "bidirectional"))
    )
    (net (code "40") (name "/D1'") (class "Default")
      (node (ref "IC19") (pin "14") (pinfunction "DO_14") (pintype "bidirectional"))
      (node (ref "IC19") (pin "2") (pinfunction "DI_2") (pintype "bidirectional"))
      (node (ref "IC3") (pin "26") (pinfunction "D1_26") (pintype "bidirectional"))
      (node (ref "R2") (pin "1") (pinfunction "1_1") (pintype "passive"))
    )
    (net (code "41") (name "/D2") (class "Default")
      (node (ref "IC1") (pin "12") (pinfunction "D2_12") (pintype "bidirectional"))
      (node (ref "IC10") (pin "7") (pinfunction "Y3_7") (pintype "tri_state"))
      (node (ref "IC2") (pin "13") (pinfunction "O2_13") (pintype "tri_state"))
      (node (ref "IC21") (pin "15") (pinfunction "I/O3_15") (pintype "bidirectional"))
      (node (ref "IC23") (pin "15") (pinfunction "I/O3_15") (pintype "bidirectional"))
      (node (ref "R19") (pin "1") (pinfunction "1_1") (pintype "passive"))
      (node (ref "R3") (pin "2") (pinfunction "2_2") (pintype "passive"))
      (node (ref "U$1") (pin "8B") (pinfunction "EDGE_8B") (pintype "bidirectional"))
    )
    (net (code "42") (name "/D2'") (class "Default")
      (node (ref "IC18") (pin "14") (pinfunction "DO_14") (pintype "bidirectional"))
      (node (ref "IC18") (pin "2") (pinfunction "DI_2") (pintype "bidirectional"))
      (node (ref "IC3") (pin "27") (pinfunction "D2_27") (pintype "bidirectional"))
      (node (ref "R3") (pin "1") (pinfunction "1_1") (pintype "passive"))
    )
    (net (code "43") (name "/D3") (class "Default")
      (node (ref "IC1") (pin "8") (pinfunction "D3_8") (pintype "bidirectional"))
      (node (ref "IC10") (pin "9") (pinfunction "Y4_9") (pintype "tri_state"))
      (node (ref "IC2") (pin "15") (pinfunction "O3_15") (pintype "tri_state"))
      (node (ref "IC21") (pin "17") (pinfunction "I/O4_17") (pintype "bidirectional"))
      (node (ref "IC23") (pin "17") (pinfunction "I/O4_17") (pintype "bidirectional"))
      (node (ref "R20") (pin "1") (pinfunction "1_1") (pintype "passive"))
      (node (ref "R4") (pin "2") (pinfunction "2_2") (pintype "passive"))
      (node (ref "U$1") (pin "11B") (pinfunction "EDGE_11B") (pintype "bidirectional"))
    )
    (net (code "44") (name "/D3'") (class "Default")
      (node (ref "IC17") (pin "14") (pinfunction "DO_14") (pintype "bidirectional"))
      (node (ref "IC17") (pin "2") (pinfunction "DI_2") (pintype "bidirectional"))
      (node (ref "IC3") (pin "28") (pinfunction "D3_28") (pintype "bidirectional"))
      (node (ref "R4") (pin "1") (pinfunction "1_1") (pintype "passive"))
    )
    (net (code "45") (name "/D4") (class "Default")
      (node (ref "IC1") (pin "7") (pinfunction "D4_7") (pintype "bidirectional"))
      (node (ref "IC10") (pin "11") (pinfunction "Y5_11") (pintype "tri_state"))
      (node (ref "IC2") (pin "16") (pinfunction "O4_16") (pintype "tri_state"))
      (node (ref "IC22") (pin "2") (pinfunction "I/O1_2") (pintype "bidirectional"))
      (node (ref "IC24") (pin "2") (pinfunction "I/O1_2") (pintype "bidirectional"))
      (node (ref "R21") (pin "1") (pinfunction "1_1") (pintype "passive"))
      (node (ref "R5") (pin "2") (pinfunction "2_2") (pintype "passive"))
      (node (ref "U$1") (pin "12B") (pinfunction "EDGE_12B") (pintype "bidirectional"))
    )
    (net (code "46") (name "/D4'") (class "Default")
      (node (ref "IC16") (pin "14") (pinfunction "DO_14") (pintype "bidirectional"))
      (node (ref "IC16") (pin "2") (pinfunction "DI_2") (pintype "bidirectional"))
      (node (ref "IC3") (pin "29") (pinfunction "D4_29") (pintype "bidirectional"))
      (node (ref "R5") (pin "1") (pinfunction "1_1") (pintype "passive"))
    )
    (net (code "47") (name "/D5") (class "Default")
      (node (ref "IC1") (pin "9") (pinfunction "D5_9") (pintype "bidirectional"))
      (node (ref "IC2") (pin "17") (pinfunction "O5_17") (pintype "tri_state"))
      (node (ref "IC22") (pin "3") (pinfunction "I/O2_3") (pintype "bidirectional"))
      (node (ref "IC24") (pin "3") (pinfunction "I/O2_3") (pintype "bidirectional"))
      (node (ref "R22") (pin "1") (pinfunction "1_1") (pintype "passive"))
      (node (ref "R6") (pin "2") (pinfunction "2_2") (pintype "passive"))
      (node (ref "U$1") (pin "10B") (pinfunction "EDGE_10B") (pintype "bidirectional"))
    )
    (net (code "48") (name "/D5'") (class "Default")
      (node (ref "IC15") (pin "14") (pinfunction "DO_14") (pintype "bidirectional"))
      (node (ref "IC15") (pin "2") (pinfunction "DI_2") (pintype "bidirectional"))
      (node (ref "IC3") (pin "30") (pinfunction "D5_30") (pintype "bidirectional"))
      (node (ref "R6") (pin "1") (pinfunction "1_1") (pintype "passive"))
    )
    (net (code "49") (name "/D6") (class "Default")
      (node (ref "IC1") (pin "10") (pinfunction "D6_10") (pintype "bidirectional"))
      (node (ref "IC10") (pin "13") (pinfunction "Y6_13") (pintype "tri_state"))
      (node (ref "IC2") (pin "18") (pinfunction "O6_18") (pintype "tri_state"))
      (node (ref "IC22") (pin "15") (pinfunction "I/O3_15") (pintype "bidirectional"))
      (node (ref "IC24") (pin "15") (pinfunction "I/O3_15") (pintype "bidirectional"))
      (node (ref "R23") (pin "1") (pinfunction "1_1") (pintype "passive"))
      (node (ref "R7") (pin "2") (pinfunction "2_2") (pintype "passive"))
      (node (ref "U$1") (pin "9B") (pinfunction "EDGE_9B") (pintype "bidirectional"))
    )
    (net (code "50") (name "/D6'") (class "Default")
      (node (ref "IC14") (pin "14") (pinfunction "DO_14") (pintype "bidirectional"))
      (node (ref "IC14") (pin "2") (pinfunction "DI_2") (pintype "bidirectional"))
      (node (ref "IC3") (pin "31") (pinfunction "D6_31") (pintype "bidirectional"))
      (node (ref "R7") (pin "1") (pinfunction "1_1") (pintype "passive"))
    )
    (net (code "51") (name "/D7") (class "Default")
      (node (ref "D1") (pin "A") (pinfunction "A_A") (pintype "bidirectional"))
      (node (ref "IC1") (pin "13") (pinfunction "D7_13") (pintype "bidirectional"))
      (node (ref "IC2") (pin "19") (pinfunction "O7_19") (pintype "tri_state"))
      (node (ref "IC22") (pin "17") (pinfunction "I/O4_17") (pintype "bidirectional"))
      (node (ref "IC24") (pin "17") (pinfunction "I/O4_17") (pintype "bidirectional"))
      (node (ref "R24") (pin "1") (pinfunction "1_1") (pintype "passive"))
      (node (ref "R8") (pin "2") (pinfunction "2_2") (pintype "passive"))
      (node (ref "U$1") (pin "3B") (pinfunction "EDGE_3B") (pintype "bidirectional"))
    )
    (net (code "52") (name "/D7'") (class "Default")
      (node (ref "IC13") (pin "14") (pinfunction "DO_14") (pintype "bidirectional"))
      (node (ref "IC13") (pin "2") (pinfunction "DI_2") (pintype "bidirectional"))
      (node (ref "IC3") (pin "32") (pinfunction "D7_32") (pintype "bidirectional"))
      (node (ref "R8") (pin "1") (pinfunction "1_1") (pintype "passive"))
    )
    (net (code "53") (name "/MREQ'") (class "Default")
      (node (ref "D10") (pin "C") (pinfunction "K_C") (pintype "bidirectional"))
      (node (ref "IC3") (pin "15") (pinfunction "~{MREQ}_15") (pintype "input"))
      (node (ref "R34") (pin "2") (pinfunction "2_2") (pintype "passive"))
    )
    (net (code "54") (name "/N$33") (class "Default")
      (node (ref "C26") (pin "1") (pinfunction "1_1") (pintype "passive"))
      (node (ref "C27") (pin "1") (pinfunction "1_1") (pintype "passive"))
      (node (ref "IC13") (pin "1") (pinfunction "VBB_1") (pintype "input"))
      (node (ref "IC14") (pin "1") (pinfunction "VBB_1") (pintype "input"))
      (node (ref "IC15") (pin "1") (pinfunction "VBB_1") (pintype "input"))
      (node (ref "IC16") (pin "1") (pinfunction "VBB_1") (pintype "input"))
      (node (ref "IC17") (pin "1") (pinfunction "VBB_1") (pintype "input"))
      (node (ref "IC18") (pin "1") (pinfunction "VBB_1") (pintype "input"))
      (node (ref "IC19") (pin "1") (pinfunction "VBB_1") (pintype "input"))
      (node (ref "IC20") (pin "1") (pinfunction "VBB_1") (pintype "input"))
      (node (ref "J3") (pin "2") (pinfunction "2_2") (pintype "passive"))
    )
    (net (code "55") (name "/RESET") (class "Default")
      (node (ref "D10") (pin "A") (pinfunction "A_A") (pintype "bidirectional"))
      (node (ref "IC28") (pin "12") (pinfunction "O_12") (pintype "output"))
    )
    (net (code "56") (name "/SNDIN") (class "Default")
      (node (ref "C54") (pin "1") (pinfunction "1_1") (pintype "passive"))
      (node (ref "C57") (pin "1") (pinfunction "1_1") (pintype "passive"))
      (node (ref "D13") (pin "A") (pinfunction "A_A") (pintype "bidirectional"))
      (node (ref "D14") (pin "C") (pinfunction "C_C") (pintype "passive"))
      (node (ref "Q7") (pin "2") (pinfunction "B_2") (pintype "passive"))
      (node (ref "R40") (pin "1") (pinfunction "1_1") (pintype "passive"))
      (node (ref "R41") (pin "2") (pinfunction "2_2") (pintype "passive"))
      (node (ref "R42") (pin "2") (pinfunction "2_2") (pintype "passive"))
      (node (ref "TP3") (pin "1") (pinfunction "TP_1") (pintype "input"))
    )
    (net (code "57") (name "/{slash}INT") (class "Default")
      (node (ref "IC1") (pin "16") (pinfunction "~{INT}_16") (pintype "input"))
      (node (ref "R25") (pin "2") (pinfunction "2_2") (pintype "passive"))
      (node (ref "TP10") (pin "1") (pinfunction "TP_1") (pintype "input"))
      (node (ref "U$1") (pin "13B") (pinfunction "EDGE_13B") (pintype "bidirectional"))
    )
    (net (code "58") (name "/~{A}{slash}B") (class "Default")
      (node (ref "IC27") (pin "3") (pinfunction "O_3") (pintype "output"))
      (node (ref "IC6") (pin "1") (pinfunction "~{A}/B_1") (pintype "input"))
      (node (ref "IC7") (pin "1") (pinfunction "~{A}/B_1") (pintype "input"))
      (node (ref "R45") (pin "1") (pinfunction "1_1") (pintype "passive"))
    )
    (net (code "59") (name "/~{CAS0}") (class "Default")
      (node (ref "IC23") (pin "1") (pinfunction "~{OE}_1") (pintype "input"))
      (node (ref "IC23") (pin "16") (pinfunction "~{CAS}_16") (pintype "input"))
      (node (ref "IC24") (pin "1") (pinfunction "~{OE}_1") (pintype "input"))
      (node (ref "IC24") (pin "16") (pinfunction "~{CAS}_16") (pintype "input"))
      (node (ref "IC25") (pin "8") (pinfunction "O_8") (pintype "output"))
    )
    (net (code "60") (name "/~{CAS1}") (class "Default")
      (node (ref "IC21") (pin "1") (pinfunction "~{OE}_1") (pintype "input"))
      (node (ref "IC21") (pin "16") (pinfunction "~{CAS}_16") (pintype "input"))
      (node (ref "IC22") (pin "1") (pinfunction "~{OE}_1") (pintype "input"))
      (node (ref "IC22") (pin "16") (pinfunction "~{CAS}_16") (pintype "input"))
      (node (ref "IC25") (pin "6") (pinfunction "O_6") (pintype "output"))
    )
    (net (code "61") (name "/~{IORQGE}") (class "Default")
      (node (ref "IC3") (pin "2") (pinfunction "~{CS}_2") (pintype "input"))
      (node (ref "Q1") (pin "1") (pinfunction "E_1") (pintype "passive"))
      (node (ref "R27") (pin "2") (pinfunction "2_2") (pintype "passive"))
      (node (ref "U$1") (pin "13A") (pinfunction "EDGE_13A") (pintype "bidirectional"))
    )
    (net (code "62") (name "/~{IORQ}") (class "Default")
      (node (ref "IC1") (pin "20") (pinfunction "~{IORQ}_20") (pintype "output"))
      (node (ref "R27") (pin "1") (pinfunction "1_1") (pintype "passive"))
      (node (ref "U$1") (pin "17B") (pinfunction "EDGE_17B") (pintype "bidirectional"))
    )
    (net (code "63") (name "/~{KBD}") (class "Default")
      (node (ref "D1") (pin "C") (pinfunction "K_C") (pintype "bidirectional"))
      (node (ref "IC10") (pin "1") (pinfunction "G1_1") (pintype "input"))
      (node (ref "IC3") (pin "10") (pinfunction "~{KBD}_10") (pintype "output"))
    )
    (net (code "64") (name "/~{MREQ}") (class "Default")
      (node (ref "IC1") (pin "19") (pinfunction "~{MREQ}_19") (pintype "output"))
      (node (ref "IC2") (pin "22") (pinfunction "~{OE}_22") (pintype "input"))
      (node (ref "IC27") (pin "4") (pinfunction "I0_4") (pintype "input"))
      (node (ref "R34") (pin "1") (pinfunction "1_1") (pintype "passive"))
      (node (ref "U$1") (pin "16B") (pinfunction "EDGE_16B") (pintype "bidirectional"))
    )
    (net (code "65") (name "/~{RAS}") (class "Default")
      (node (ref "IC21") (pin "5") (pinfunction "~{RAS}_5") (pintype "input"))
      (node (ref "IC22") (pin "5") (pinfunction "~{RAS}_5") (pintype "input"))
      (node (ref "IC23") (pin "5") (pinfunction "~{RAS}_5") (pintype "input"))
      (node (ref "IC24") (pin "5") (pinfunction "~{RAS}_5") (pintype "input"))
      (node (ref "IC27") (pin "6") (pinfunction "O_6") (pintype "output"))
      (node (ref "IC27") (pin "9") (pinfunction "I0_9") (pintype "input"))
      (node (ref "R28") (pin "1") (pinfunction "1_1") (pintype "passive"))
    )
    (net (code "66") (name "/~{RD}") (class "Default")
      (node (ref "IC1") (pin "21") (pinfunction "~{RD}_21") (pintype "output"))
      (node (ref "IC25") (pin "2") (pinfunction "I1_2") (pintype "input"))
      (node (ref "IC3") (pin "17") (pinfunction "~{RD}_17") (pintype "input"))
      (node (ref "J1") (pin "3") (pinfunction "3_3") (pintype "passive"))
      (node (ref "U$1") (pin "18B") (pinfunction "EDGE_18B") (pintype "bidirectional"))
    )
    (net (code "67") (name "/~{RESET}") (class "Default")
      (node (ref "C17") (pin "1") (pinfunction "1_1") (pintype "passive"))
      (node (ref "IC1") (pin "26") (pinfunction "~{RESET}_26") (pintype "input"))
      (node (ref "IC28") (pin "13") (pinfunction "I_13") (pintype "input"))
      (node (ref "R29") (pin "1") (pinfunction "1_1") (pintype "passive"))
      (node (ref "U$1") (pin "20A") (pinfunction "EDGE_20A") (pintype "bidirectional"))
    )
    (net (code "68") (name "/~{RFSH}") (class "Default")
      (node (ref "IC1") (pin "28") (pinfunction "~{RFSH}_28") (pintype "output"))
      (node (ref "IC26") (pin "13") (pinfunction "I1_13") (pintype "input"))
      (node (ref "IC26") (pin "2") (pinfunction "I1_2") (pintype "input"))
      (node (ref "IC5") (pin "11") (pinfunction "CLK_11") (pintype "input"))
      (node (ref "U$1") (pin "25B") (pinfunction "EDGE_25B") (pintype "bidirectional"))
    )
    (net (code "69") (name "/~{ROMCS}") (class "Default")
      (node (ref "IC2") (pin "20") (pinfunction "~{CE}_20") (pintype "input"))
      (node (ref "R26") (pin "2") (pinfunction "2_2") (pintype "passive"))
      (node (ref "TP9") (pin "1") (pinfunction "TP_1") (pintype "input"))
      (node (ref "U$1") (pin "25A") (pinfunction "EDGE_25A") (pintype "bidirectional"))
    )
    (net (code "70") (name "/~{ULAINT}") (class "Default")
      (node (ref "IC3") (pin "34") (pinfunction "~{INT}_34") (pintype "output"))
      (node (ref "R25") (pin "1") (pinfunction "1_1") (pintype "passive"))
    )
    (net (code "71") (name "/~{VCAS}") (class "Default")
      (node (ref "IC13") (pin "15") (pinfunction "~{CAS}_15") (pintype "input"))
      (node (ref "IC14") (pin "15") (pinfunction "~{CAS}_15") (pintype "input"))
      (node (ref "IC15") (pin "15") (pinfunction "~{CAS}_15") (pintype "input"))
      (node (ref "IC16") (pin "15") (pinfunction "~{CAS}_15") (pintype "input"))
      (node (ref "IC17") (pin "15") (pinfunction "~{CAS}_15") (pintype "input"))
      (node (ref "IC18") (pin "15") (pinfunction "~{CAS}_15") (pintype "input"))
      (node (ref "IC19") (pin "15") (pinfunction "~{CAS}_15") (pintype "input"))
      (node (ref "IC20") (pin "15") (pinfunction "~{CAS}_15") (pintype "input"))
      (node (ref "IC3") (pin "12") (pinfunction "~{VCAS}_12") (pintype "output"))
      (node (ref "TP5") (pin "1") (pinfunction "TP_1") (pintype "input"))
    )
    (net (code "72") (name "/~{VRAS}") (class "Default")
      (node (ref "IC13") (pin "4") (pinfunction "~{RAS}_4") (pintype "input"))
      (node (ref "IC14") (pin "4") (pinfunction "~{RAS}_4") (pintype "input"))
      (node (ref "IC15") (pin "4") (pinfunction "~{RAS}_4") (pintype "input"))
      (node (ref "IC16") (pin "4") (pinfunction "~{RAS}_4") (pintype "input"))
      (node (ref "IC17") (pin "4") (pinfunction "~{RAS}_4") (pintype "input"))
      (node (ref "IC18") (pin "4") (pinfunction "~{RAS}_4") (pintype "input"))
      (node (ref "IC19") (pin "4") (pinfunction "~{RAS}_4") (pintype "input"))
      (node (ref "IC20") (pin "4") (pinfunction "~{RAS}_4") (pintype "input"))
      (node (ref "IC3") (pin "13") (pinfunction "~{VRAS}_13") (pintype "output"))
      (node (ref "R16") (pin "2") (pinfunction "2_2") (pintype "passive"))
      (node (ref "TP4") (pin "1") (pinfunction "TP_1") (pintype "input"))
    )
    (net (code "73") (name "/~{VWR}") (class "Default")
      (node (ref "IC13") (pin "3") (pinfunction "~{WE}_3") (pintype "input"))
      (node (ref "IC14") (pin "3") (pinfunction "~{WE}_3") (pintype "input"))
      (node (ref "IC15") (pin "3") (pinfunction "~{WE}_3") (pintype "input"))
      (node (ref "IC16") (pin "3") (pinfunction "~{WE}_3") (pintype "input"))
      (node (ref "IC17") (pin "3") (pinfunction "~{WE}_3") (pintype "input"))
      (node (ref "IC18") (pin "3") (pinfunction "~{WE}_3") (pintype "input"))
      (node (ref "IC19") (pin "3") (pinfunction "~{WE}_3") (pintype "input"))
      (node (ref "IC20") (pin "3") (pinfunction "~{WE}_3") (pintype "input"))
      (node (ref "IC3") (pin "14") (pinfunction "~{VWR}_14") (pintype "output"))
      (node (ref "TP6") (pin "1") (pinfunction "TP_1") (pintype "input"))
    )
    (net (code "74") (name "/~{WR}") (class "Default")
      (node (ref "IC1") (pin "22") (pinfunction "~{WR}_22") (pintype "output"))
      (node (ref "IC21") (pin "4") (pinfunction "~{WE}_4") (pintype "input"))
      (node (ref "IC22") (pin "4") (pinfunction "~{WE}_4") (pintype "input"))
      (node (ref "IC23") (pin "4") (pinfunction "~{WE}_4") (pintype "input"))
      (node (ref "IC24") (pin "4") (pinfunction "~{WE}_4") (pintype "input"))
      (node (ref "IC25") (pin "1") (pinfunction "I0_1") (pintype "input"))
      (node (ref "IC3") (pin "16") (pinfunction "~{WR}_16") (pintype "input"))
      (node (ref "U$1") (pin "19B") (pinfunction "EDGE_19B") (pintype "bidirectional"))
    )
    (net (code "75") (name "AUDIO") (class "Default")
      (node (ref "C36") (pin "2") (pinfunction "2_2") (pintype "passive"))
      (node (ref "C54") (pin "2") (pinfunction "2_2") (pintype "passive"))
      (node (ref "C55") (pin "1") (pinfunction "1_1") (pintype "passive"))
      (node (ref "D25_") (pin "A") (pinfunction "A_A") (pintype "bidirectional"))
      (node (ref "J4") (pin "1") (pinfunction "1_1") (pintype "passive"))
      (node (ref "R53") (pin "1") (pinfunction "1_1") (pintype "passive"))
      (node (ref "R54") (pin "2") (pinfunction "2_2") (pintype "passive"))
    )
    (net (code "76") (name "GND") (class "Default")
      (node (ref "7805") (pin "GND") (pinfunction "GND_GND") (pintype "input"))
      (node (ref "C1") (pin "-") (pinfunction "-_-") (pintype "passive"))
      (node (ref "C10") (pin "2") (pinfunction "2_2") (pintype "passive"))
      (node (ref "C11") (pin "2") (pinfunction "2_2") (pintype "passive"))
      (node (ref "C12") (pin "1") (pinfunction "1_1") (pintype "passive"))
      (node (ref "C13") (pin "1") (pinfunction "1_1") (pintype "passive"))
      (node (ref "C14") (pin "1") (pinfunction "1_1") (pintype "passive"))
      (node (ref "C15") (pin "2") (pinfunction "2_2") (pintype "passive"))
      (node (ref "C16") (pin "2") (pinfunction "2_2") (pintype "passive"))
      (node (ref "C17") (pin "2") (pinfunction "2_2") (pintype "passive"))
      (node (ref "C18") (pin "2") (pinfunction "2_2") (pintype "passive"))
      (node (ref "C19") (pin "2") (pinfunction "2_2") (pintype "passive"))
      (node (ref "C2") (pin "-") (pinfunction "-_-") (pintype "passive"))
      (node (ref "C20") (pin "2") (pinfunction "2_2") (pintype "passive"))
      (node (ref "C21") (pin "2") (pinfunction "2_2") (pintype "passive"))
      (node (ref "C22") (pin "1") (pinfunction "1_1") (pintype "passive"))
      (node (ref "C23") (pin "2") (pinfunction "2_2") (pintype "passive"))
      (node (ref "C24") (pin "1") (pinfunction "1_1") (pintype "passive"))
      (node (ref "C25") (pin "2") (pinfunction "2_2") (pintype "passive"))
      (node (ref "C26") (pin "2") (pinfunction "2_2") (pintype "passive"))
      (node (ref "C27") (pin "2") (pinfunction "2_2") (pintype "passive"))
      (node (ref "C28") (pin "2") (pinfunction "2_2") (pintype "passive"))
      (node (ref "C29") (pin "1") (pinfunction "1_1") (pintype "passive"))
      (node (ref "C3") (pin "1") (pinfunction "1_1") (pintype "passive"))
      (node (ref "C30") (pin "2") (pinfunction "2_2") (pintype "passive"))
      (node (ref "C31") (pin "1") (pinfunction "1_1") (pintype "passive"))
      (node (ref "C32") (pin "1") (pinfunction "1_1") (pintype "passive"))
      (node (ref "C33") (pin "1") (pinfunction "1_1") (pintype "passive"))
      (node (ref "C40") (pin "1") (pinfunction "1_1") (pintype "passive"))
      (node (ref "C43") (pin "1") (pinfunction "1_1") (pintype "passive"))
      (node (ref "C44") (pin "2") (pinfunction "2_2") (pintype "passive"))
      (node (ref "C45") (pin "2") (pinfunction "2_2") (pintype "passive"))
      (node (ref "C46") (pin "2") (pinfunction "2_2") (pintype "passive"))
      (node (ref "C49") (pin "+") (pinfunction "+_+") (pintype "passive"))
      (node (ref "C50") (pin "2") (pinfunction "2_2") (pintype "passive"))
      (node (ref "C52") (pin "-") (pinfunction "-_-") (pintype "passive"))
      (node (ref "C53") (pin "-") (pinfunction "-_-") (pintype "passive"))
      (node (ref "C56") (pin "1") (pinfunction "1_1") (pintype "passive"))
      (node (ref "C57") (pin "2") (pinfunction "2_2") (pintype "passive"))
      (node (ref "C6") (pin "1") (pinfunction "1_1") (pintype "passive"))
      (node (ref "C8") (pin "1") (pinfunction "1_1") (pintype "passive"))
      (node (ref "D14") (pin "A") (pinfunction "A_A") (pintype "passive"))
      (node (ref "D16") (pin "A") (pinfunction "A_A") (pintype "bidirectional"))
      (node (ref "D18") (pin "A") (pinfunction "A_A") (pintype "bidirectional"))
      (node (ref "D20") (pin "C") (pinfunction "K_C") (pintype "bidirectional"))
      (node (ref "D21") (pin "C") (pinfunction "K_C") (pintype "bidirectional"))
      (node (ref "D24") (pin "A") (pinfunction "A_A") (pintype "bidirectional"))
      (node (ref "EAR") (pin "RING") (pinfunction "SHIELD_RING") (pintype "passive"))
      (node (ref "IC1") (pin "29") (pinfunction "GND_29") (pintype "power_in"))
      (node (ref "IC10") (pin "15") (pinfunction "G2_15") (pintype "input"))
      (node (ref "IC10") (pin "8") (pinfunction "GND_8") (pintype "power_in"))
      (node (ref "IC11") (pin "10") (pinfunction "GND_10") (pintype "power_in"))
      (node (ref "IC12") (pin "5") (pinfunction "GND_5") (pintype "power_in"))
      (node (ref "IC13") (pin "16") (pinfunction "VSS_16") (pintype "power_in"))
      (node (ref "IC14") (pin "16") (pinfunction "VSS_16") (pintype "power_in"))
      (node (ref "IC15") (pin "16") (pinfunction "VSS_16") (pintype "power_in"))
      (node (ref "IC16") (pin "16") (pinfunction "VSS_16") (pintype "power_in"))
      (node (ref "IC17") (pin "16") (pinfunction "VSS_16") (pintype "power_in"))
      (node (ref "IC18") (pin "16") (pinfunction "VSS_16") (pintype "power_in"))
      (node (ref "IC19") (pin "16") (pinfunction "VSS_16") (pintype "power_in"))
      (node (ref "IC2") (pin "14") (pinfunction "GND_14") (pintype "power_in"))
      (node (ref "IC20") (pin "16") (pinfunction "VSS_16") (pintype "power_in"))
      (node (ref "IC21") (pin "18") (pinfunction "GND_18") (pintype "power_in"))
      (node (ref "IC22") (pin "18") (pinfunction "GND_18") (pintype "power_in"))
      (node (ref "IC23") (pin "18") (pinfunction "GND_18") (pintype "power_in"))
      (node (ref "IC24") (pin "18") (pinfunction "GND_18") (pintype "power_in"))
      (node (ref "IC25") (pin "7") (pinfunction "GND_7") (pintype "power_in"))
      (node (ref "IC26") (pin "7") (pinfunction "GND_7") (pintype "power_in"))
      (node (ref "IC27") (pin "5") (pinfunction "I1_5") (pintype "input"))
      (node (ref "IC27") (pin "7") (pinfunction "GND_7") (pintype "power_in"))
      (node (ref "IC28") (pin "7") (pinfunction "GND_7") (pintype "power_in"))
      (node (ref "IC3") (pin "20") (pinfunction "GND_20") (pintype "power_in"))
      (node (ref "IC4") (pin "7") (pinfunction "GND_7") (pintype "power_in"))
      (node (ref "IC5") (pin "7") (pinfunction "GND_7") (pintype "power_in"))
      (node (ref "IC6") (pin "15") (pinfunction "G_15") (pintype "input"))
      (node (ref "IC6") (pin "8") (pinfunction "GND_8") (pintype "power_in"))
      (node (ref "IC7") (pin "15") (pinfunction "G_15") (pintype "input"))
      (node (ref "IC7") (pin "8") (pinfunction "GND_8") (pintype "power_in"))
      (node (ref "IC8") (pin "15") (pinfunction "G_15") (pintype "input"))
      (node (ref "IC8") (pin "8") (pinfunction "GND_8") (pintype "power_in"))
      (node (ref "IC9") (pin "15") (pinfunction "G_15") (pintype "input"))
      (node (ref "IC9") (pin "8") (pinfunction "GND_8") (pintype "power_in"))
      (node (ref "MIC") (pin "RING") (pinfunction "SHIELD_RING") (pintype "passive"))
      (node (ref "Q2") (pin "1") (pinfunction "E_1") (pintype "passive"))
      (node (ref "Q4") (pin "1") (pinfunction "E_1") (pintype "passive"))
      (node (ref "Q6") (pin "C") (pinfunction "C_C") (pintype "passive"))
      (node (ref "Q7") (pin "1") (pinfunction "E_1") (pintype "passive"))
      (node (ref "R33") (pin "2") (pinfunction "2_2") (pintype "passive"))
      (node (ref "R41") (pin "1") (pinfunction "1_1") (pintype "passive"))
      (node (ref "R47") (pin "1") (pinfunction "1_1") (pintype "passive"))
      (node (ref "R50") (pin "1") (pinfunction "1_1") (pintype "passive"))
      (node (ref "R53") (pin "2") (pinfunction "2_2") (pintype "passive"))
      (node (ref "R55") (pin "2") (pinfunction "2_2") (pintype "passive"))
      (node (ref "R65") (pin "2") (pinfunction "2_2") (pintype "passive"))
      (node (ref "R69") (pin "1") (pinfunction "1_1") (pintype "passive"))
      (node (ref "R70") (pin "1") (pinfunction "1_1") (pintype "passive"))
      (node (ref "R73_") (pin "2") (pinfunction "2_2") (pintype "passive"))
      (node (ref "R76") (pin "2") (pinfunction "2_2") (pintype "passive"))
      (node (ref "U$1") (pin "14A") (pinfunction "EDGE_14A") (pintype "bidirectional"))
      (node (ref "U$1") (pin "6A") (pinfunction "EDGE_6A") (pintype "bidirectional"))
      (node (ref "U$1") (pin "7A") (pinfunction "EDGE_7A") (pintype "bidirectional"))
      (node (ref "X1") (pin "SHELL") (pinfunction "2_SHELL") (pintype "passive"))
      (node (ref "X1") (pin "SHELL@1") (pinfunction "2_SHELL@1") (pintype "passive"))
      (node (ref "X1") (pin "SHELL@2") (pinfunction "2_SHELL@2") (pintype "passive"))
      (node (ref "X2") (pin "RING") (pinfunction "SHIELD_RING") (pintype "passive"))
    )
    (net (code "77") (name "Net-(C5-Pad+)") (class "Default")
      (node (ref "C5") (pin "+") (pinfunction "+_+") (pintype "passive"))
      (node (ref "R42") (pin "1") (pinfunction "1_1") (pintype "passive"))
    )
    (net (code "78") (name "Net-(C5-Pad-)") (class "Default")
      (node (ref "C5") (pin "-") (pinfunction "-_-") (pintype "passive"))
      (node (ref "EAR") (pin "TIP") (pinfunction "TIP_TIP") (pintype "passive"))
      (node (ref "J5") (pin "1") (pinfunction "1_1") (pintype "passive"))
      (node (ref "R70") (pin "2") (pinfunction "2_2") (pintype "passive"))
    )
    (net (code "79") (name "Net-(C7-Pad1)") (class "Default")
      (node (ref "C7") (pin "1") (pinfunction "1_1") (pintype "passive"))
      (node (ref "XTAL") (pin "2") (pinfunction "2_2") (pintype "passive"))
    )
    (net (code "80") (name "Net-(C8-Pad2)") (class "Default")
      (node (ref "C8") (pin "2") (pinfunction "2_2") (pintype "passive"))
      (node (ref "Q3") (pin "B") (pinfunction "B_B") (pintype "passive"))
      (node (ref "R44") (pin "2") (pinfunction "2_2") (pintype "passive"))
      (node (ref "XTAL") (pin "1") (pinfunction "1_1") (pintype "passive"))
    )
    (net (code "81") (name "Net-(C37-Pad1)") (class "Default")
      (node (ref "C37") (pin "1") (pinfunction "1_1") (pintype "passive"))
      (node (ref "C38") (pin "2") (pinfunction "2_2") (pintype "passive"))
      (node (ref "R55") (pin "1") (pinfunction "1_1") (pintype "passive"))
    )
    (net (code "82") (name "Net-(C38-Pad1)") (class "Default")
      (node (ref "C38") (pin "1") (pinfunction "1_1") (pintype "passive"))
      (node (ref "C39") (pin "2") (pinfunction "2_2") (pintype "passive"))
      (node (ref "R56") (pin "1") (pinfunction "1_1") (pintype "passive"))
    )
    (net (code "83") (name "Net-(C39-Pad1)") (class "Default")
      (node (ref "C39") (pin "1") (pinfunction "1_1") (pintype "passive"))
      (node (ref "L2") (pin "2") (pinfunction "2_2") (pintype "passive"))
    )
    (net (code "84") (name "Net-(C49-Pad-)") (class "Default")
      (node (ref "C49") (pin "-") (pinfunction "-_-") (pintype "passive"))
      (node (ref "D19") (pin "A") (pinfunction "A_A") (pintype "bidirectional"))
      (node (ref "R67") (pin "2") (pinfunction "2_2") (pintype "passive"))
    )
    (net (code "85") (name "Net-(C56-Pad2)") (class "Default")
      (node (ref "C56") (pin "2") (pinfunction "2_2") (pintype "passive"))
      (node (ref "L2") (pin "1") (pinfunction "1_1") (pintype "passive"))
      (node (ref "R71") (pin "1") (pinfunction "1_1") (pintype "passive"))
      (node (ref "R72") (pin "2") (pinfunction "2_2") (pintype "passive"))
    )
    (net (code "86") (name "Net-(C58-Pad+)") (class "Default")
      (node (ref "C58") (pin "+") (pinfunction "+_+") (pintype "passive"))
      (node (ref "R77") (pin "2") (pinfunction "2_2") (pintype "passive"))
    )
    (net (code "87") (name "Net-(D2-PadA)") (class "Default")
      (node (ref "D2") (pin "A") (pinfunction "A_A") (pintype "bidirectional"))
      (node (ref "KB2") (pin "3") (pinfunction "3_3") (pintype "passive"))
    )
    (net (code "88") (name "Net-(D3-PadA)") (class "Default")
      (node (ref "D3") (pin "A") (pinfunction "A_A") (pintype "bidirectional"))
      (node (ref "KB2") (pin "6") (pinfunction "6_6") (pintype "passive"))
    )
    (net (code "89") (name "Net-(D4-PadA)") (class "Default")
      (node (ref "D4") (pin "A") (pinfunction "A_A") (pintype "bidirectional"))
      (node (ref "KB2") (pin "7") (pinfunction "7_7") (pintype "passive"))
    )
    (net (code "90") (name "Net-(D7-PadA)") (class "Default")
      (node (ref "D7") (pin "A") (pinfunction "A_A") (pintype "bidirectional"))
      (node (ref "KB2") (pin "4") (pinfunction "4_4") (pintype "passive"))
    )
    (net (code "91") (name "Net-(D8-PadA)") (class "Default")
      (node (ref "D8") (pin "A") (pinfunction "A_A") (pintype "bidirectional"))
      (node (ref "KB2") (pin "2") (pinfunction "2_2") (pintype "passive"))
    )
    (net (code "92") (name "Net-(D9-PadA)") (class "Default")
      (node (ref "D9") (pin "A") (pinfunction "A_A") (pintype "bidirectional"))
      (node (ref "KB2") (pin "1") (pinfunction "1_1") (pintype "passive"))
    )
    (net (code "93") (name "Net-(D11-K)") (class "Default")
      (node (ref "D11") (pin "C") (pinfunction "K_C") (pintype "bidirectional"))
      (node (ref "D12") (pin "C") (pinfunction "K_C") (pintype "bidirectional"))
      (node (ref "IC27") (pin "11") (pinfunction "O_11") (pintype "output"))
      (node (ref "R26") (pin "1") (pinfunction "1_1") (pintype "passive"))
      (node (ref "R33") (pin "1") (pinfunction "1_1") (pintype "passive"))
    )
    (net (code "94") (name "Net-(D16-K)") (class "Default")
      (node (ref "C36") (pin "1") (pinfunction "1_1") (pintype "passive"))
      (node (ref "D15") (pin "A") (pinfunction "A_A") (pintype "bidirectional"))
      (node (ref "D16") (pin "C") (pinfunction "K_C") (pintype "bidirectional"))
      (node (ref "IC3") (pin "24") (pinfunction "BEEP_24") (pintype "output"))
      (node (ref "TP7") (pin "1") (pinfunction "TP_1") (pintype "input"))
    )
    (net (code "95") (name "Net-(D19-K)") (class "Default")
      (node (ref "C48") (pin "2") (pinfunction "2_2") (pintype "passive"))
      (node (ref "D19") (pin "C") (pinfunction "K_C") (pintype "bidirectional"))
      (node (ref "D20") (pin "A") (pinfunction "A_A") (pintype "bidirectional"))
    )
    (net (code "96") (name "Net-(D22-K)") (class "Default")
      (node (ref "C51") (pin "2") (pinfunction "2_2") (pintype "passive"))
      (node (ref "D22") (pin "C") (pinfunction "K_C") (pintype "bidirectional"))
      (node (ref "D23") (pin "A") (pinfunction "A_A") (pintype "bidirectional"))
    )
    (net (code "97") (name "Net-(D23-K)") (class "Default")
      (node (ref "C52") (pin "+") (pinfunction "+_+") (pintype "passive"))
      (node (ref "D23") (pin "C") (pinfunction "K_C") (pintype "bidirectional"))
      (node (ref "R68") (pin "2") (pinfunction "2_2") (pintype "passive"))
    )
    (net (code "98") (name "Net-(D27-K)") (class "Default")
      (node (ref "D25") (pin "C") (pinfunction "C_C") (pintype "passive"))
      (node (ref "D26") (pin "C") (pinfunction "C_C") (pintype "passive"))
      (node (ref "D27") (pin "C") (pinfunction "K_C") (pintype "bidirectional"))
      (node (ref "IC3") (pin "18") (pinfunction "BRIGHT_18") (pintype "output"))
    )
    (net (code "99") (name "Net-(EAR-PadNC)") (class "Default")
      (node (ref "EAR") (pin "NC") (pinfunction "NC_NC") (pintype "passive"))
      (node (ref "J5") (pin "2") (pinfunction "2_2") (pintype "passive"))
    )
    (net (code "100") (name "Net-(IC1-CLK)") (class "Default")
      (node (ref "IC1") (pin "6") (pinfunction "CLK_6") (pintype "input"))
      (node (ref "Q2") (pin "3") (pinfunction "C_3") (pintype "passive"))
      (node (ref "R48") (pin "1") (pinfunction "1_1") (pintype "passive"))
      (node (ref "TP1") (pin "1") (pinfunction "TP_1") (pintype "input"))
    )
    (net (code "101") (name "Net-(IC1-~{BUSAK})") (class "Default")
      (node (ref "IC1") (pin "23") (pinfunction "~{BUSAK}_23") (pintype "output"))
      (node (ref "U$1") (pin "26A") (pinfunction "EDGE_26A") (pintype "bidirectional"))
    )
    (net (code "102") (name "Net-(IC1-~{BUSRQ})") (class "Default")
      (node (ref "IC1") (pin "25") (pinfunction "~{BUSRQ}_25") (pintype "input"))
      (node (ref "R30") (pin "2") (pinfunction "2_2") (pintype "passive"))
      (node (ref "U$1") (pin "19A") (pinfunction "EDGE_19A") (pintype "bidirectional"))
    )
    (net (code "103") (name "Net-(IC1-~{HALT})") (class "Default")
      (node (ref "IC1") (pin "18") (pinfunction "~{HALT}_18") (pintype "output"))
      (node (ref "U$1") (pin "15B") (pinfunction "EDGE_15B") (pintype "bidirectional"))
    )
    (net (code "104") (name "Net-(IC1-~{M1})") (class "Default")
      (node (ref "IC1") (pin "27") (pinfunction "~{M1}_27") (pintype "output"))
      (node (ref "U$1") (pin "24B") (pinfunction "EDGE_24B") (pintype "bidirectional"))
    )
    (net (code "105") (name "Net-(IC1-~{NMI})") (class "Default")
      (node (ref "IC1") (pin "17") (pinfunction "~{NMI}_17") (pintype "input"))
      (node (ref "R31") (pin "2") (pinfunction "2_2") (pintype "passive"))
      (node (ref "U$1") (pin "14B") (pinfunction "EDGE_14B") (pintype "bidirectional"))
    )
    (net (code "106") (name "Net-(IC1-~{WAIT})") (class "Default")
      (node (ref "IC1") (pin "24") (pinfunction "~{WAIT}_24") (pintype "input"))
      (node (ref "R32") (pin "2") (pinfunction "2_2") (pintype "passive"))
      (node (ref "U$1") (pin "21B") (pinfunction "EDGE_21B") (pintype "bidirectional"))
    )
    (net (code "107") (name "Net-(IC2-~{PGM})") (class "Default")
      (node (ref "IC2") (pin "27") (pinfunction "~{PGM}_27") (pintype "input"))
      (node (ref "J1") (pin "2") (pinfunction "2_2") (pintype "passive"))
    )
    (net (code "108") (name "Net-(IC3-MIC)") (class "Default")
      (node (ref "IC3") (pin "23") (pinfunction "MIC_23") (pintype "output"))
      (node (ref "R46") (pin "2") (pinfunction "2_2") (pintype "passive"))
    )
    (net (code "109") (name "Net-(IC4B-D)") (class "Default")
      (node (ref "IC4") (pin "12") (pinfunction "D_12") (pintype "input"))
      (node (ref "IC4") (pin "8") (pinfunction "~{Q}_8") (pintype "output"))
    )
    (net (code "110") (name "Net-(IC5A-CLK)") (class "Default")
      (node (ref "IC5") (pin "3") (pinfunction "CLK_3") (pintype "input"))
      (node (ref "IC5") (pin "9") (pinfunction "Q_9") (pintype "output"))
    )
    (net (code "111") (name "Net-(IC5A-D)") (class "Default")
      (node (ref "IC5") (pin "2") (pinfunction "D_2") (pintype "input"))
      (node (ref "IC5") (pin "6") (pinfunction "~{Q}_6") (pintype "output"))
    )
    (net (code "112") (name "Net-(IC8A-1Y)") (class "Default")
      (node (ref "IC8") (pin "4") (pinfunction "1Y_4") (pintype "output"))
      (node (ref "R15") (pin "2") (pinfunction "2_2") (pintype "passive"))
    )
    (net (code "113") (name "Net-(IC8A-2Y)") (class "Default")
      (node (ref "IC8") (pin "7") (pinfunction "2Y_7") (pintype "output"))
      (node (ref "R14") (pin "2") (pinfunction "2_2") (pintype "passive"))
    )
    (net (code "114") (name "Net-(IC8A-3Y)") (class "Default")
      (node (ref "IC8") (pin "9") (pinfunction "3Y_9") (pintype "output"))
      (node (ref "R12") (pin "2") (pinfunction "2_2") (pintype "passive"))
    )
    (net (code "115") (name "Net-(IC8A-4Y)") (class "Default")
      (node (ref "IC8") (pin "12") (pinfunction "4Y_12") (pintype "output"))
      (node (ref "R13") (pin "2") (pinfunction "2_2") (pintype "passive"))
    )
    (net (code "116") (name "Net-(IC8A-~{A}{slash}B)") (class "Default")
      (node (ref "IC8") (pin "1") (pinfunction "~{A}/B_1") (pintype "input"))
      (node (ref "IC9") (pin "1") (pinfunction "~{A}/B_1") (pintype "input"))
      (node (ref "R16") (pin "1") (pinfunction "1_1") (pintype "passive"))
    )
    (net (code "117") (name "Net-(IC9A-2Y)") (class "Default")
      (node (ref "IC9") (pin "7") (pinfunction "2Y_7") (pintype "output"))
      (node (ref "R11") (pin "2") (pinfunction "2_2") (pintype "passive"))
    )
    (net (code "118") (name "Net-(IC9A-3Y)") (class "Default")
      (node (ref "IC9") (pin "9") (pinfunction "3Y_9") (pintype "output"))
      (node (ref "R9") (pin "2") (pinfunction "2_2") (pintype "passive"))
    )
    (net (code "119") (name "Net-(IC9A-4Y)") (class "Default")
      (node (ref "IC9") (pin "12") (pinfunction "4Y_12") (pintype "output"))
      (node (ref "R10") (pin "2") (pinfunction "2_2") (pintype "passive"))
    )
    (net (code "120") (name "Net-(IC10A-A1)") (class "Default")
      (node (ref "IC10") (pin "2") (pinfunction "A1_2") (pintype "input"))
      (node (ref "KB1") (pin "5") (pinfunction "5_5") (pintype "passive"))
      (node (ref "P") (pin "6") (pinfunction "M_6") (pintype "passive"))
      (node (ref "R39") (pin "2") (pinfunction "2_2") (pintype "passive"))
    )
    (net (code "121") (name "Net-(IC10A-A2)") (class "Default")
      (node (ref "IC10") (pin "4") (pinfunction "A2_4") (pintype "input"))
      (node (ref "KB1") (pin "4") (pinfunction "4_4") (pintype "passive"))
      (node (ref "P") (pin "1") (pinfunction "M_1") (pintype "passive"))
      (node (ref "R38") (pin "2") (pinfunction "2_2") (pintype "passive"))
    )
    (net (code "122") (name "Net-(IC10A-A3)") (class "Default")
      (node (ref "IC10") (pin "6") (pinfunction "A3_6") (pintype "input"))
      (node (ref "KB1") (pin "3") (pinfunction "3_3") (pintype "passive"))
      (node (ref "P") (pin "2") (pinfunction "M_2") (pintype "passive"))
      (node (ref "R35") (pin "2") (pinfunction "2_2") (pintype "passive"))
    )
    (net (code "123") (name "Net-(IC10A-A4)") (class "Default")
      (node (ref "IC10") (pin "10") (pinfunction "A4_10") (pintype "input"))
      (node (ref "KB1") (pin "2") (pinfunction "2_2") (pintype "passive"))
      (node (ref "P") (pin "4") (pinfunction "M_4") (pintype "passive"))
      (node (ref "R36") (pin "2") (pinfunction "2_2") (pintype "passive"))
    )
    (net (code "124") (name "Net-(IC10A-A5)") (class "Default")
      (node (ref "IC10") (pin "12") (pinfunction "A5_12") (pintype "input"))
      (node (ref "KB1") (pin "1") (pinfunction "1_1") (pintype "passive"))
      (node (ref "P") (pin "3") (pinfunction "M_3") (pintype "passive"))
      (node (ref "R37") (pin "2") (pinfunction "2_2") (pintype "passive"))
    )
    (net (code "125") (name "Net-(IC10A-A6)") (class "Default")
      (node (ref "IC10") (pin "14") (pinfunction "A6_14") (pintype "input"))
      (node (ref "Q7") (pin "3") (pinfunction "C_3") (pintype "passive"))
      (node (ref "R74_") (pin "1") (pinfunction "1_1") (pintype "passive"))
    )
    (net (code "126") (name "Net-(IC11-B-Y)") (class "Default")
      (node (ref "C45") (pin "1") (pinfunction "1_1") (pintype "passive"))
      (node (ref "IC11") (pin "4") (pinfunction "B-Y_4") (pintype "output"))
      (node (ref "IC12") (pin "4") (pinfunction "B-Y_4") (pintype "input"))
    )
    (net (code "127") (name "Net-(IC11-B1)") (class "Default")
      (node (ref "IC11") (pin "17") (pinfunction "B3_17") (pintype "input"))
      (node (ref "IC11") (pin "19") (pinfunction "B1_19") (pintype "input"))
      (node (ref "IC3") (pin "22") (pinfunction "BLUE_22") (pintype "output"))
      (node (ref "R75") (pin "2") (pinfunction "2_2") (pintype "passive"))
    )
    (net (code "128") (name "Net-(IC11-B2)") (class "Default")
      (node (ref "D27") (pin "A") (pinfunction "A_A") (pintype "bidirectional"))
      (node (ref "IC11") (pin "18") (pinfunction "B2_18") (pintype "input"))
      (node (ref "R75") (pin "1") (pinfunction "1_1") (pintype "passive"))
    )
    (net (code "129") (name "Net-(IC11-BLANK)") (class "Default")
      (node (ref "IC11") (pin "8") (pinfunction "SYNC_8") (pintype "input"))
      (node (ref "IC11") (pin "9") (pinfunction "BLANK_9") (pintype "input"))
      (node (ref "IC3") (pin "33") (pinfunction "SYNC_33") (pintype "output"))
      (node (ref "TP8") (pin "1") (pinfunction "TP_1") (pintype "input"))
    )
    (net (code "130") (name "Net-(IC11-CREF)") (class "Default")
      (node (ref "C46") (pin "1") (pinfunction "1_1") (pintype "passive"))
      (node (ref "IC11") (pin "7") (pinfunction "CREF_7") (pintype "input"))
      (node (ref "IC12") (pin "12") (pinfunction "Y_12") (pintype "input"))
    )
    (net (code "131") (name "Net-(IC11-G1)") (class "Default")
      (node (ref "IC11") (pin "14") (pinfunction "G3_14") (pintype "input"))
      (node (ref "IC11") (pin "16") (pinfunction "G1_16") (pintype "input"))
      (node (ref "IC3") (pin "19") (pinfunction "GREEN_19") (pintype "output"))
      (node (ref "R73") (pin "2") (pinfunction "2_2") (pintype "passive"))
    )
    (net (code "132") (name "Net-(IC11-G2)") (class "Default")
      (node (ref "D25") (pin "A") (pinfunction "A_A") (pintype "passive"))
      (node (ref "IC11") (pin "15") (pinfunction "G2_15") (pintype "input"))
      (node (ref "R73") (pin "1") (pinfunction "1_1") (pintype "passive"))
    )
    (net (code "133") (name "Net-(IC11-GATE)") (class "Default")
      (node (ref "IC11") (pin "1") (pinfunction "GATE_1") (pintype "input"))
      (node (ref "IC28") (pin "6") (pinfunction "O_6") (pintype "output"))
    )
    (net (code "134") (name "Net-(IC11-H{slash}2)") (class "Default")
      (node (ref "IC11") (pin "2") (pinfunction "H/2_2") (pintype "input"))
      (node (ref "IC4") (pin "9") (pinfunction "Q_9") (pintype "output"))
    )
    (net (code "135") (name "Net-(IC11-R-Y)") (class "Default")
      (node (ref "C44") (pin "1") (pinfunction "1_1") (pintype "passive"))
      (node (ref "IC11") (pin "3") (pinfunction "R-Y_3") (pintype "output"))
      (node (ref "IC12") (pin "2") (pinfunction "R-Y_2") (pintype "input"))
    )
    (net (code "136") (name "Net-(IC11-R1)") (class "Default")
      (node (ref "IC11") (pin "11") (pinfunction "R3_11") (pintype "input"))
      (node (ref "IC11") (pin "13") (pinfunction "R1_13") (pintype "input"))
      (node (ref "IC3") (pin "21") (pinfunction "RED_21") (pintype "output"))
      (node (ref "R74") (pin "2") (pinfunction "2_2") (pintype "passive"))
    )
    (net (code "137") (name "Net-(IC11-R2)") (class "Default")
      (node (ref "D26") (pin "A") (pinfunction "A_A") (pintype "passive"))
      (node (ref "IC11") (pin "12") (pinfunction "R2_12") (pintype "input"))
      (node (ref "R74") (pin "1") (pinfunction "1_1") (pintype "passive"))
    )
    (net (code "138") (name "Net-(IC11-Y)") (class "Default")
      (node (ref "IC11") (pin "6") (pinfunction "Y_6") (pintype "output"))
      (node (ref "R63") (pin "2") (pinfunction "2_2") (pintype "passive"))
    )
    (net (code "139") (name "Net-(IC12-CHB_O)") (class "Default")
      (node (ref "IC12") (pin "10") (pinfunction "CHB_O_10") (pintype "input"))
      (node (ref "R59") (pin "2") (pinfunction "2_2") (pintype "passive"))
    )
    (net (code "140") (name "Net-(IC12-CR_LAG)") (class "Default")
      (node (ref "C40") (pin "2") (pinfunction "2_2") (pintype "passive"))
      (node (ref "IC12") (pin "18") (pinfunction "CR_LAG_18") (pintype "output"))
      (node (ref "R56") (pin "2") (pinfunction "2_2") (pintype "passive"))
    )
    (net (code "141") (name "Net-(IC12-CR_LEAD)") (class "Default")
      (node (ref "C37") (pin "2") (pinfunction "2_2") (pintype "passive"))
      (node (ref "IC12") (pin "1") (pinfunction "CR_LEAD_1") (pintype "input"))
    )
    (net (code "142") (name "Net-(IC12-CR_OSC)") (class "Default")
      (node (ref "IC12") (pin "17") (pinfunction "CR_OSC_17") (pintype "input"))
      (node (ref "R72") (pin "1") (pinfunction "1_1") (pintype "passive"))
      (node (ref "R73_") (pin "1") (pinfunction "1_1") (pintype "passive"))
    )
    (net (code "143") (name "Net-(IC12-CR_SUBC)") (class "Default")
      (node (ref "IC12") (pin "13") (pinfunction "CR_SUBC_13") (pintype "input"))
      (node (ref "Q8") (pin "2") (pinfunction "B_2") (pintype "passive"))
      (node (ref "R63") (pin "1") (pinfunction "1_1") (pintype "passive"))
    )
    (net (code "144") (name "Net-(IC12-SNDTK)") (class "Default")
      (node (ref "D25_") (pin "K") (pinfunction "K_K") (pintype "bidirectional"))
      (node (ref "IC12") (pin "15") (pinfunction "SNDTK_15") (pintype "input"))
      (node (ref "L1") (pin "4") (pinfunction "E_4") (pintype "passive"))
    )
    (net (code "145") (name "Net-(IC12-TNKA1)") (class "Default")
      (node (ref "IC12") (pin "8") (pinfunction "TNKA1_8") (pintype "output"))
      (node (ref "IC12") (pin "9") (pinfunction "TNKA2_9") (pintype "input"))
    )
    (net (code "146") (name "Net-(IC12-TNKB1)") (class "Default")
      (node (ref "C41") (pin "2") (pinfunction "2_2") (pintype "passive"))
      (node (ref "IC12") (pin "6") (pinfunction "TNKB1_6") (pintype "output"))
      (node (ref "L3") (pin "1") (pinfunction "1_1") (pintype "passive"))
      (node (ref "R57") (pin "2") (pinfunction "2_2") (pintype "passive"))
    )
    (net (code "147") (name "Net-(IC12-TNKB2)") (class "Default")
      (node (ref "C41") (pin "1") (pinfunction "1_1") (pintype "passive"))
      (node (ref "IC12") (pin "7") (pinfunction "TNKB2_7") (pintype "input"))
      (node (ref "L3") (pin "2") (pinfunction "2_2") (pintype "passive"))
      (node (ref "R58") (pin "2") (pinfunction "2_2") (pintype "passive"))
    )
    (net (code "148") (name "Net-(IC25A-O)") (class "Default")
      (node (ref "IC25") (pin "12") (pinfunction "I0_12") (pintype "input"))
      (node (ref "IC25") (pin "3") (pinfunction "O_3") (pintype "output"))
    )
    (net (code "149") (name "Net-(IC25B-I1)") (class "Default")
      (node (ref "IC25") (pin "10") (pinfunction "I1_10") (pintype "input"))
      (node (ref "IC25") (pin "5") (pinfunction "I1_5") (pintype "input"))
      (node (ref "IC28") (pin "4") (pinfunction "O_4") (pintype "output"))
    )
    (net (code "150") (name "Net-(IC25C-I0)") (class "Default")
      (node (ref "IC25") (pin "9") (pinfunction "I0_9") (pintype "input"))
      (node (ref "IC28") (pin "2") (pinfunction "O_2") (pintype "output"))
    )
    (net (code "151") (name "Net-(IC25D-O)") (class "Default")
      (node (ref "IC25") (pin "11") (pinfunction "O_11") (pintype "output"))
      (node (ref "IC27") (pin "1") (pinfunction "I0_1") (pintype "input"))
    )
    (net (code "152") (name "Net-(IC26A-O)") (class "Default")
      (node (ref "IC26") (pin "3") (pinfunction "O_3") (pintype "output"))
      (node (ref "IC26") (pin "4") (pinfunction "I0_4") (pintype "input"))
    )
    (net (code "153") (name "Net-(IC26B-I1)") (class "Default")
      (node (ref "IC26") (pin "5") (pinfunction "I1_5") (pintype "input"))
      (node (ref "IC5") (pin "5") (pinfunction "Q_5") (pintype "output"))
    )
    (net (code "154") (name "Net-(IC26B-O)") (class "Default")
      (node (ref "IC26") (pin "6") (pinfunction "O_6") (pintype "output"))
      (node (ref "IC26") (pin "9") (pinfunction "I0_9") (pintype "input"))
    )
    (net (code "155") (name "Net-(IC26C-I1)") (class "Default")
      (node (ref "IC26") (pin "10") (pinfunction "I1_10") (pintype "input"))
      (node (ref "IC26") (pin "11") (pinfunction "O_11") (pintype "output"))
    )
    (net (code "156") (name "Net-(IC27A-I1)") (class "Default")
      (node (ref "C10") (pin "1") (pinfunction "1_1") (pintype "passive"))
      (node (ref "IC27") (pin "2") (pinfunction "I1_2") (pintype "input"))
      (node (ref "R28") (pin "2") (pinfunction "2_2") (pintype "passive"))
    )
    (net (code "157") (name "Net-(IC27C-I1)") (class "Default")
      (node (ref "C11") (pin "1") (pinfunction "1_1") (pintype "passive"))
      (node (ref "IC27") (pin "10") (pinfunction "I1_10") (pintype "input"))
      (node (ref "R45") (pin "2") (pinfunction "2_2") (pintype "passive"))
    )
    (net (code "158") (name "Net-(IC27C-O)") (class "Default")
      (node (ref "IC27") (pin "8") (pinfunction "O_8") (pintype "output"))
      (node (ref "IC28") (pin "3") (pinfunction "I_3") (pintype "input"))
    )
    (net (code "159") (name "Net-(IC28C-I)") (class "Default")
      (node (ref "IC28") (pin "5") (pinfunction "I_5") (pintype "input"))
      (node (ref "IC3") (pin "35") (pinfunction "GATE_35") (pintype "output"))
      (node (ref "IC4") (pin "11") (pinfunction "CLK_11") (pintype "input"))
    )
    (net (code "160") (name "Net-(IC28D-I)") (class "Default")
      (node (ref "C6") (pin "2") (pinfunction "2_2") (pintype "passive"))
      (node (ref "C7") (pin "2") (pinfunction "2_2") (pintype "passive"))
      (node (ref "IC28") (pin "9") (pinfunction "I_9") (pintype "input"))
      (node (ref "Q3") (pin "C") (pinfunction "C_C") (pintype "passive"))
      (node (ref "R43") (pin "1") (pinfunction "1_1") (pintype "passive"))
      (node (ref "R44") (pin "1") (pinfunction "1_1") (pintype "passive"))
    )
    (net (code "161") (name "Net-(IC28D-O)") (class "Default")
      (node (ref "IC28") (pin "11") (pinfunction "I_11") (pintype "input"))
      (node (ref "IC28") (pin "8") (pinfunction "O_8") (pintype "output"))
      (node (ref "JP") (pin "3") (pinfunction "3_3") (pintype "passive"))
    )
    (net (code "162") (name "Net-(IC28E-O)") (class "Default")
      (node (ref "IC28") (pin "10") (pinfunction "O_10") (pintype "output"))
      (node (ref "IC3") (pin "11") (pinfunction "CLK_11") (pintype "input"))
      (node (ref "JP") (pin "1") (pinfunction "1_1") (pintype "passive"))
      (node (ref "JP") (pin "2") (pinfunction "2_2") (pintype "passive"))
      (node (ref "TP2") (pin "1") (pinfunction "TP_1") (pintype "input"))
    )
    (net (code "163") (name "Net-(J4-Pad2)") (class "Default")
      (node (ref "J4") (pin "2") (pinfunction "2_2") (pintype "passive"))
      (node (ref "MIC") (pin "TIP") (pinfunction "TIP_TIP") (pintype "passive"))
    )
    (net (code "164") (name "Net-(MIC-PadNC)") (class "Default")
      (node (ref "MIC") (pin "NC") (pinfunction "NC_NC") (pintype "passive"))
      (node (ref "R46") (pin "1") (pinfunction "1_1") (pintype "passive"))
      (node (ref "R69") (pin "2") (pinfunction "2_2") (pintype "passive"))
    )
    (net (code "165") (name "Net-(PE-M)") (class "Default")
      (node (ref "D6") (pin "A") (pinfunction "A_A") (pintype "bidirectional"))
      (node (ref "KB2") (pin "5") (pinfunction "5_5") (pintype "passive"))
      (node (ref "P") (pin "5") (pinfunction "M_5") (pintype "passive"))
      (node (ref "P") (pin "8") (pinfunction "M_8") (pintype "passive"))
      (node (ref "P") (pin "9") (pinfunction "M_9") (pintype "passive"))
    )
    (net (code "166") (name "Net-(PG-M)") (class "Default")
      (node (ref "D5") (pin "A") (pinfunction "A_A") (pintype "bidirectional"))
      (node (ref "KB2") (pin "8") (pinfunction "8_8") (pintype "passive"))
      (node (ref "P") (pin "7") (pinfunction "M_7") (pintype "passive"))
    )
    (net (code "167") (name "Net-(Q2-B)") (class "Default")
      (node (ref "C9") (pin "1") (pinfunction "1_1") (pintype "passive"))
      (node (ref "Q2") (pin "2") (pinfunction "B_2") (pintype "passive"))
      (node (ref "R49") (pin "1") (pinfunction "1_1") (pintype "passive"))
      (node (ref "R50") (pin "2") (pinfunction "2_2") (pintype "passive"))
    )
    (net (code "168") (name "Net-(Q3-PadE)") (class "Default")
      (node (ref "Q3") (pin "E") (pinfunction "E_E") (pintype "passive"))
      (node (ref "R47") (pin "2") (pinfunction "2_2") (pintype "passive"))
    )
    (net (code "169") (name "Net-(Q4-B)") (class "Default")
      (node (ref "C47") (pin "2") (pinfunction "2_2") (pintype "passive"))
      (node (ref "Q4") (pin "2") (pinfunction "B_2") (pintype "passive"))
      (node (ref "R64") (pin "1") (pinfunction "1_1") (pintype "passive"))
      (node (ref "R65") (pin "1") (pinfunction "1_1") (pintype "passive"))
    )
    (net (code "170") (name "Net-(Q4-C)") (class "Default")
      (node (ref "Q4") (pin "3") (pinfunction "C_3") (pintype "passive"))
      (node (ref "Q5") (pin "B") (pinfunction "B_B") (pintype "passive"))
      (node (ref "Q6") (pin "B") (pinfunction "B_B") (pintype "passive"))
      (node (ref "R66") (pin "2") (pinfunction "2_2") (pintype "passive"))
    )
    (net (code "171") (name "Net-(Q8-E)") (class "Default")
      (node (ref "Q8") (pin "1") (pinfunction "E_1") (pintype "passive"))
      (node (ref "R76") (pin "1") (pinfunction "1_1") (pintype "passive"))
      (node (ref "R77") (pin "1") (pinfunction "1_1") (pintype "passive"))
    )
    (net (code "172") (name "Net-(U$1Y-EDGE)") (class "Default")
      (node (ref "C55") (pin "2") (pinfunction "2_2") (pintype "passive"))
      (node (ref "U$1") (pin "4B") (pinfunction "EDGE_4B") (pintype "bidirectional"))
    )
    (net (code "173") (name "Net-(X1-1)") (class "Default")
      (node (ref "C58") (pin "-") (pinfunction "-_-") (pintype "passive"))
      (node (ref "X1") (pin "PIN") (pinfunction "1_PIN") (pintype "passive"))
    )
    (net (code "174") (name "V+") (class "Default")
      (node (ref "7805") (pin "IN") (pinfunction "IN_IN") (pintype "input"))
      (node (ref "C2") (pin "+") (pinfunction "+_+") (pintype "passive"))
      (node (ref "C3") (pin "2") (pinfunction "2_2") (pintype "passive"))
      (node (ref "D22") (pin "A") (pinfunction "A_A") (pintype "bidirectional"))
      (node (ref "J2") (pin "3") (pinfunction "3_3") (pintype "passive"))
      (node (ref "Q5") (pin "C") (pinfunction "C_C") (pintype "passive"))
      (node (ref "R66") (pin "1") (pinfunction "1_1") (pintype "passive"))
      (node (ref "U$1") (pin "4A") (pinfunction "EDGE_4A") (pintype "bidirectional"))
      (node (ref "X2") (pin "NC") (pinfunction "NC_NC") (pintype "passive"))
      (node (ref "X2") (pin "TIP") (pinfunction "TIP_TIP") (pintype "passive"))
    )
    (net (code "175") (name "VDD") (class "Default")
      (node (ref "C23") (pin "1") (pinfunction "1_1") (pintype "passive"))
      (node (ref "C25") (pin "1") (pinfunction "1_1") (pintype "passive"))
      (node (ref "C28") (pin "1") (pinfunction "1_1") (pintype "passive"))
      (node (ref "C30") (pin "1") (pinfunction "1_1") (pintype "passive"))
      (node (ref "IC13") (pin "8") (pinfunction "VDD_8") (pintype "power_in"))
      (node (ref "IC14") (pin "8") (pinfunction "VDD_8") (pintype "power_in"))
      (node (ref "IC15") (pin "8") (pinfunction "VDD_8") (pintype "power_in"))
      (node (ref "IC16") (pin "8") (pinfunction "VDD_8") (pintype "power_in"))
      (node (ref "IC17") (pin "8") (pinfunction "VDD_8") (pintype "power_in"))
      (node (ref "IC18") (pin "8") (pinfunction "VDD_8") (pintype "power_in"))
      (node (ref "IC19") (pin "8") (pinfunction "VDD_8") (pintype "power_in"))
      (node (ref "IC20") (pin "8") (pinfunction "VDD_8") (pintype "power_in"))
      (node (ref "J2") (pin "2") (pinfunction "2_2") (pintype "passive"))
    )
    (net (code "176") (name "unconnected-(IC3-~{50}{slash}60HZ-Pad1)") (class "Default")
      (node (ref "IC3") (pin "1") (pinfunction "~{50}/60HZ_1") (pintype "input"))
    )
    (net (code "177") (name "unconnected-(IC4A-CLK-Pad3)") (class "Default")
      (node (ref "IC4") (pin "3") (pinfunction "CLK_3") (pintype "input"))
    )
    (net (code "178") (name "unconnected-(IC4A-CLR-Pad1)") (class "Default")
      (node (ref "IC4") (pin "1") (pinfunction "CLR_1") (pintype "input"))
    )
    (net (code "179") (name "unconnected-(IC4A-D-Pad2)") (class "Default")
      (node (ref "IC4") (pin "2") (pinfunction "D_2") (pintype "input"))
    )
    (net (code "180") (name "unconnected-(IC4A-PRE-Pad4)") (class "Default")
      (node (ref "IC4") (pin "4") (pinfunction "PRE_4") (pintype "input"))
    )
    (net (code "181") (name "unconnected-(IC4A-Q-Pad5)") (class "Default")
      (node (ref "IC4") (pin "5") (pinfunction "Q_5") (pintype "output"))
    )
    (net (code "182") (name "unconnected-(IC4A-~{Q}-Pad6)") (class "Default")
      (node (ref "IC4") (pin "6") (pinfunction "~{Q}_6") (pintype "output"))
    )
    (net (code "183") (name "unconnected-(IC5B-~{Q}-Pad8)") (class "Default")
      (node (ref "IC5") (pin "8") (pinfunction "~{Q}_8") (pintype "output"))
    )
    (net (code "184") (name "unconnected-(IC6A-1A-Pad2)") (class "Default")
      (node (ref "IC6") (pin "2") (pinfunction "1A_2") (pintype "input"))
    )
    (net (code "185") (name "unconnected-(IC6A-1B-Pad3)") (class "Default")
      (node (ref "IC6") (pin "3") (pinfunction "1B_3") (pintype "input"))
    )
    (net (code "186") (name "unconnected-(IC6A-1Y-Pad4)") (class "Default")
      (node (ref "IC6") (pin "4") (pinfunction "1Y_4") (pintype "output"))
    )
    (net (code "187") (name "unconnected-(IC6A-3A-Pad11)") (class "Default")
      (node (ref "IC6") (pin "11") (pinfunction "3A_11") (pintype "input"))
    )
    (net (code "188") (name "unconnected-(IC6A-3B-Pad10)") (class "Default")
      (node (ref "IC6") (pin "10") (pinfunction "3B_10") (pintype "input"))
    )
    (net (code "189") (name "unconnected-(IC6A-3Y-Pad9)") (class "Default")
      (node (ref "IC6") (pin "9") (pinfunction "3Y_9") (pintype "output"))
    )
    (net (code "190") (name "unconnected-(IC9A-1A-Pad2)") (class "Default")
      (node (ref "IC9") (pin "2") (pinfunction "1A_2") (pintype "input"))
    )
    (net (code "191") (name "unconnected-(IC9A-1B-Pad3)") (class "Default")
      (node (ref "IC9") (pin "3") (pinfunction "1B_3") (pintype "input"))
    )
    (net (code "192") (name "unconnected-(IC9A-1Y-Pad4)") (class "Default")
      (node (ref "IC9") (pin "4") (pinfunction "1Y_4") (pintype "output"))
    )
    (net (code "193") (name "unconnected-(IC12-CHA_O-Pad11)") (class "Default")
      (node (ref "IC12") (pin "11") (pinfunction "CHA_O_11") (pintype "input"))
    )
    (net (code "194") (name "unconnected-(L1B-S1-PadS2)") (class "Default")
      (node (ref "L1") (pin "S2") (pinfunction "S1_S2") (pintype "passive"))
    )
    (net (code "195") (name "unconnected-(L1B-S2-PadS1)") (class "Default")
      (node (ref "L1") (pin "S1") (pinfunction "S2_S1") (pintype "passive"))
    )
    (net (code "196") (name "unconnected-(U$1AX-EDGE-Pad28B)") (class "Default")
      (node (ref "U$1") (pin "28B") (pinfunction "EDGE_28B") (pintype "bidirectional"))
    )
    (net (code "197") (name "unconnected-(U$1F-EDGE-Pad15A)") (class "Default")
      (node (ref "U$1") (pin "15A") (pinfunction "EDGE_15A") (pintype "bidirectional"))
    )
    (net (code "198") (name "unconnected-(U$1G-EDGE-Pad16A)") (class "Default")
      (node (ref "U$1") (pin "16A") (pinfunction "EDGE_16A") (pintype "bidirectional"))
    )
    (net (code "199") (name "unconnected-(U$1H-EDGE-Pad17A)") (class "Default")
      (node (ref "U$1") (pin "17A") (pinfunction "EDGE_17A") (pintype "bidirectional"))
    )
    (net (code "200") (name "unconnected-(U$1I-EDGE-Pad18A)") (class "Default")
      (node (ref "U$1") (pin "18A") (pinfunction "EDGE_18A") (pintype "bidirectional"))
    )
  )
)
